# io-board-f-1.net
KiCad netlist of a schematic drawn in EAGLE
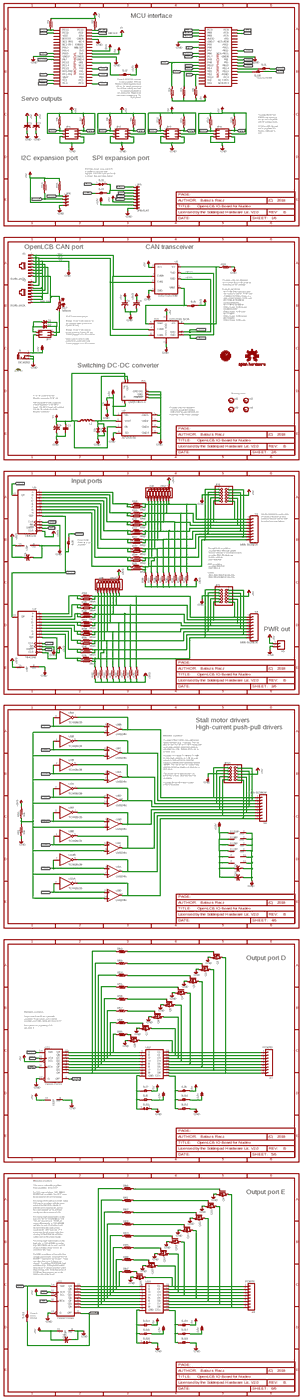
[diagram p0: schematic, sheet 1, overview]
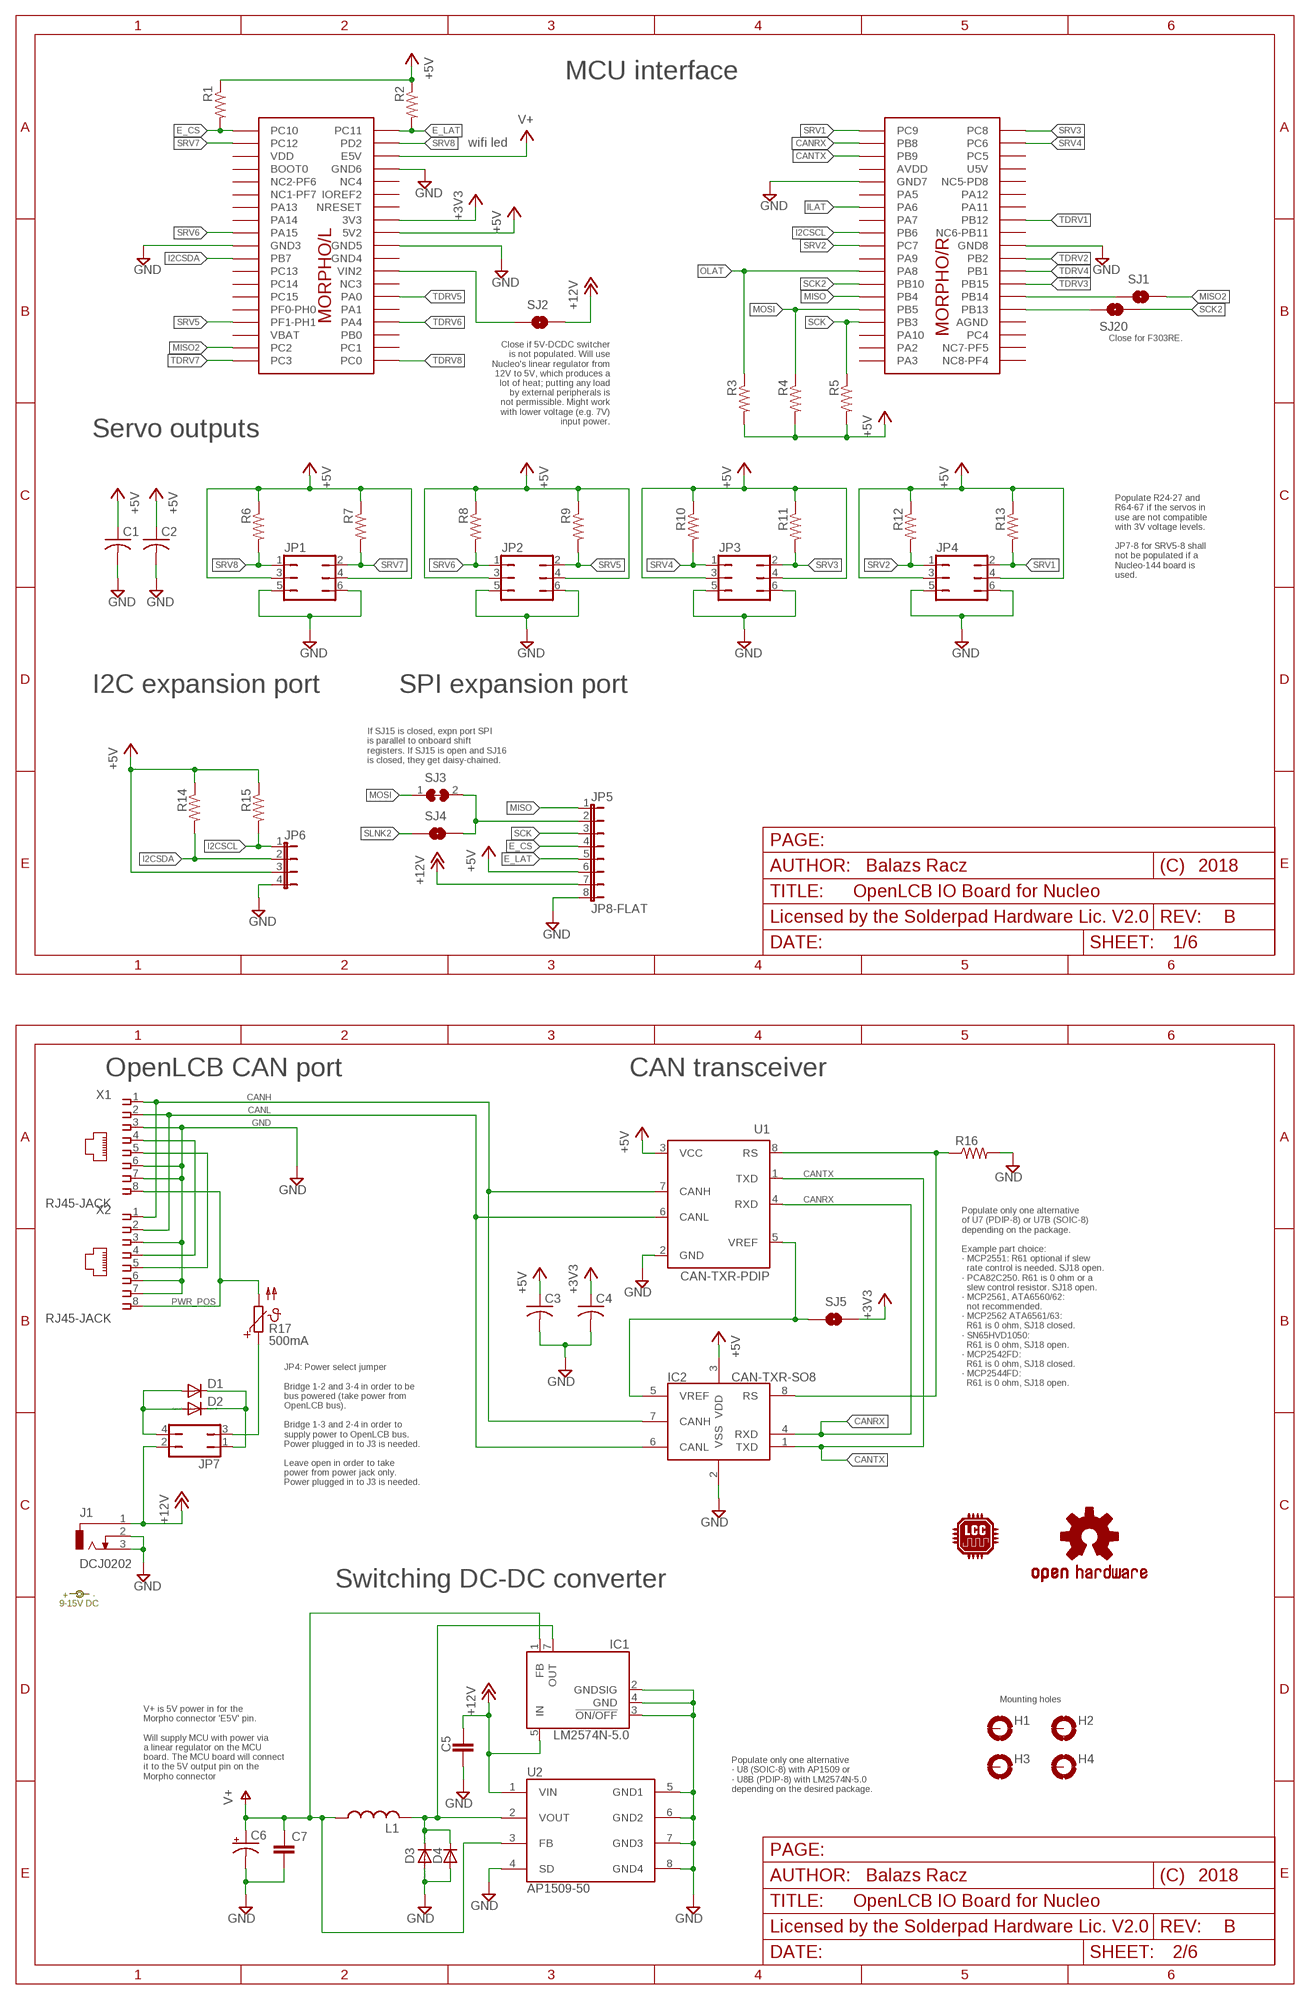
[diagram p1: schematic, sheet 1, part 1 of 4]
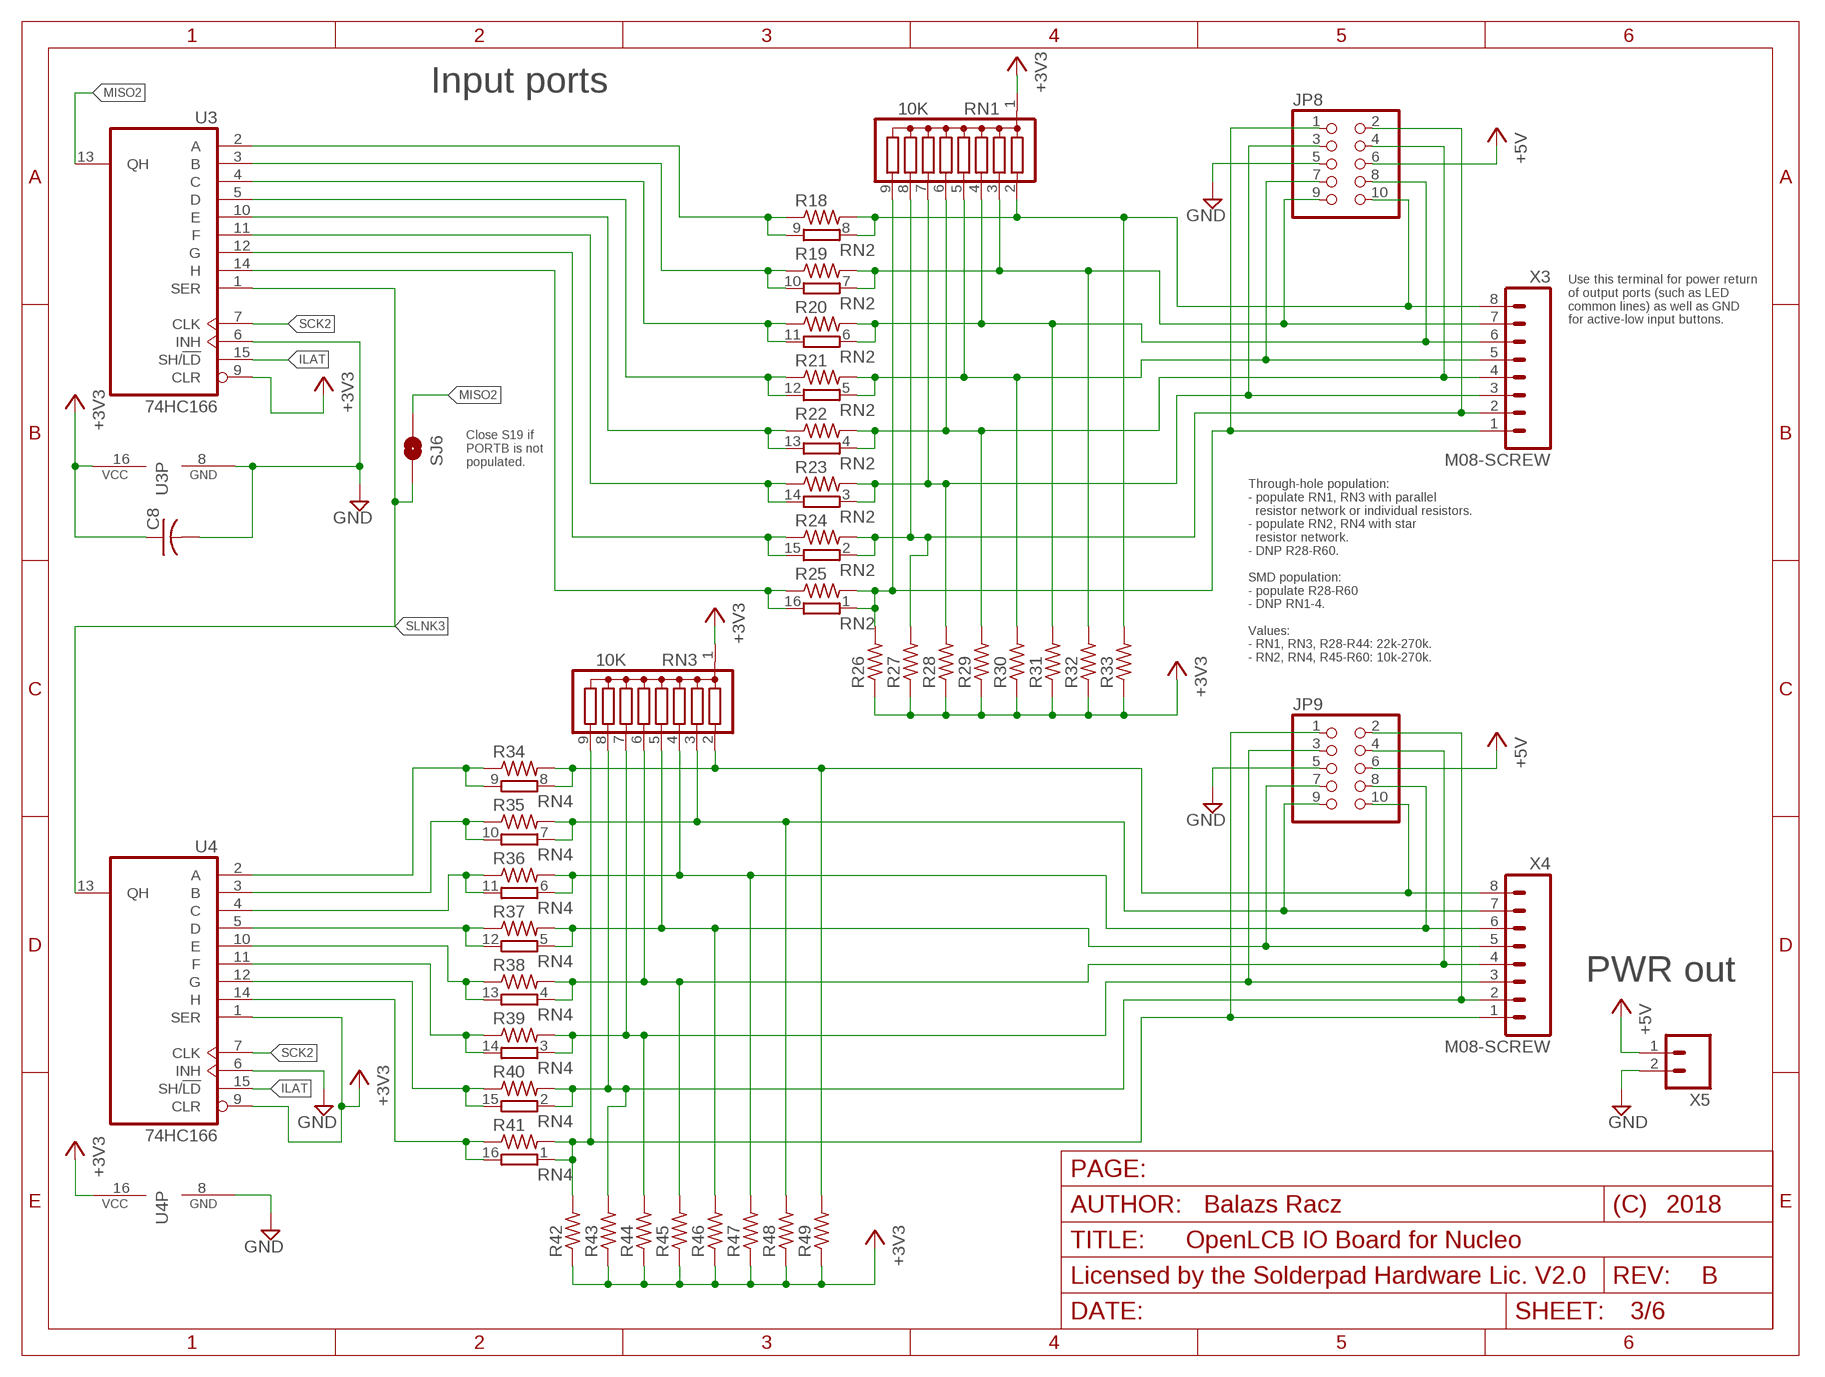
[diagram p2: schematic, sheet 1, part 2 of 4]
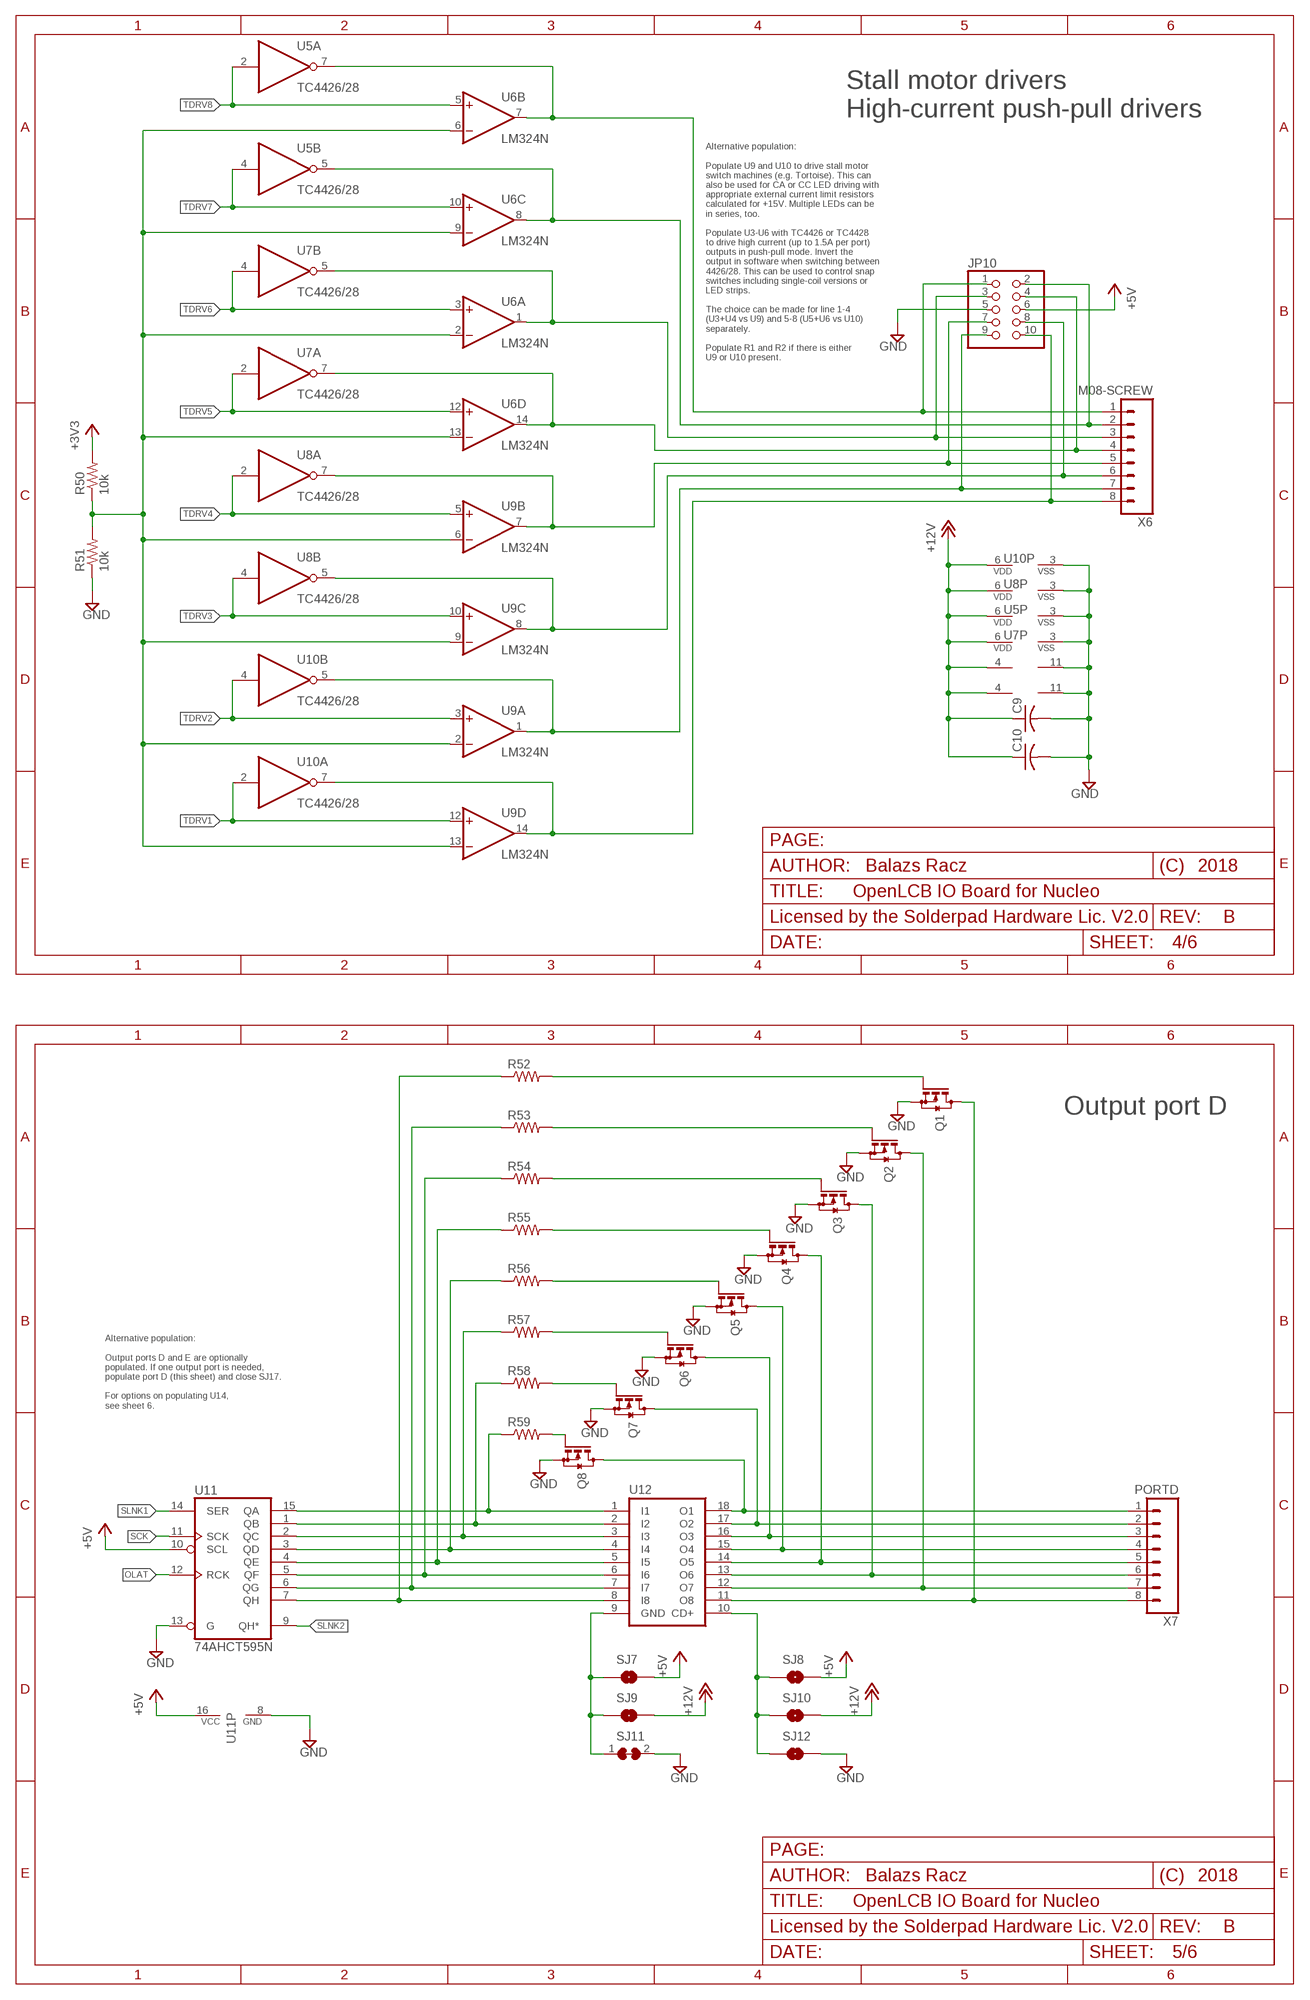
[diagram p3: schematic, sheet 1, part 3 of 4]
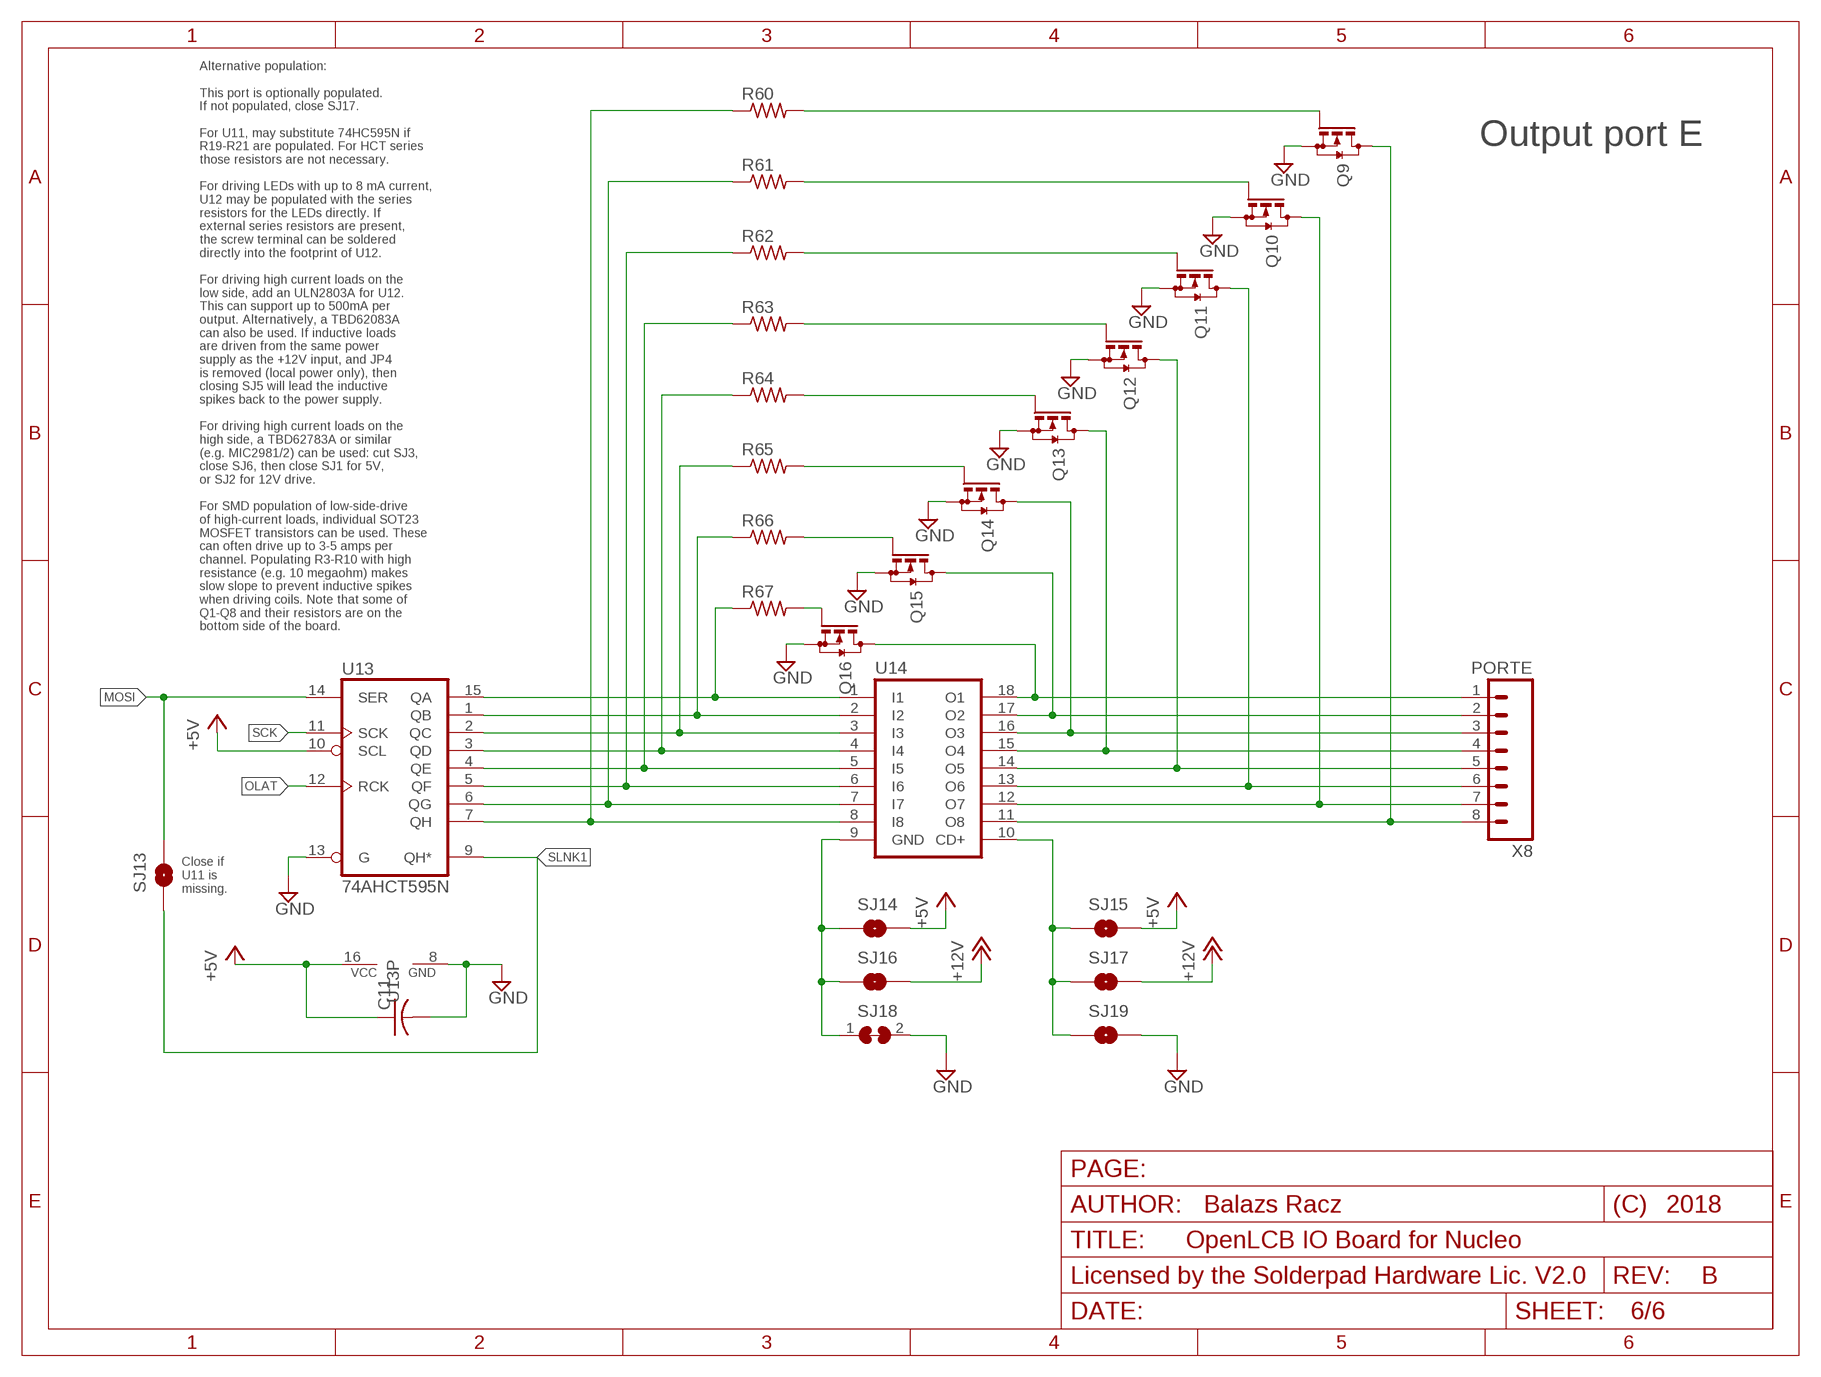
[diagram p4: schematic, sheet 1, part 4 of 4]

(export (version "E")
  (design (tool "Eeschema 10.0.6"))
  (components
    (comp (ref "C1")
      (value "C-USC1206")
      (footprint "eagle-import:C1206")
      (libsource (lib "eagle-import") (part "C-USC1206"))
    )
    (comp (ref "C2")
      (value "C-USC1206")
      (footprint "eagle-import:C1206")
      (libsource (lib "eagle-import") (part "C-USC1206"))
    )
    (comp (ref "C3")
      (value "C-USC0805")
      (footprint "eagle-import:C0805")
      (libsource (lib "eagle-import") (part "C-USC0805"))
    )
    (comp (ref "C4")
      (value "C-USC0805")
      (footprint "eagle-import:C0805")
      (libsource (lib "eagle-import") (part "C-USC0805"))
    )
    (comp (ref "C5")
      (value "C-EUC1206")
      (footprint "eagle-import:C1206")
      (libsource (lib "eagle-import") (part "C-EUC1206"))
    )
    (comp (ref "C6")
      (value "CPOL-USE2.5-5")
      (footprint "eagle-import:E2,5-5")
      (libsource (lib "eagle-import") (part "CPOL-USE2.5-5"))
    )
    (comp (ref "C7")
      (value "C-EUC1206")
      (footprint "eagle-import:C1206")
      (libsource (lib "eagle-import") (part "C-EUC1206"))
    )
    (comp (ref "C8")
      (value "C-USC0805")
      (footprint "eagle-import:C0805")
      (libsource (lib "eagle-import") (part "C-USC0805"))
    )
    (comp (ref "C9")
      (value "C-USC1206")
      (footprint "eagle-import:C1206")
      (libsource (lib "eagle-import") (part "C-USC1206"))
    )
    (comp (ref "C10")
      (value "C-USC1206")
      (footprint "eagle-import:C1206")
      (libsource (lib "eagle-import") (part "C-USC1206"))
    )
    (comp (ref "C11")
      (value "C-USC0805")
      (footprint "eagle-import:C0805")
      (libsource (lib "eagle-import") (part "C-USC0805"))
    )
    (comp (ref "D1")
      (value "DIODEDO-214AA-NODOC")
      (footprint "eagle-import:DO214AA-NODOC")
      (libsource (lib "eagle-import") (part "DIODEDO-214AA-NODOC"))
    )
    (comp (ref "D2")
      (value "DIODE-DO41-7.6")
      (footprint "eagle-import:DO41-7.6")
      (libsource (lib "eagle-import") (part "DIODE-DO41-7.6"))
    )
    (comp (ref "D3")
      (value "DIODE-DO41-7.6")
      (footprint "eagle-import:DO41-7.6")
      (libsource (lib "eagle-import") (part "DIODE-DO41-7.6"))
    )
    (comp (ref "D4")
      (value "DIODEDO-214AA-NODOC")
      (footprint "eagle-import:DO214AA-NODOC")
      (libsource (lib "eagle-import") (part "DIODEDO-214AA-NODOC"))
    )
    (comp (ref "G1")
      (value "NUCLEO_64_GENERIC")
      (footprint "eagle-import:NUCLEO_BRD_BASE64")
      (libsource (lib "eagle-import") (part "NUCLEO_64_GENERIC"))
    )
    (comp (ref "H1")
      (value "MOUNT-PAD-ROUND3.3")
      (footprint "eagle-import:3,3-PAD")
      (libsource (lib "eagle-import") (part "MOUNT-PAD-ROUND3.3"))
    )
    (comp (ref "H2")
      (value "MOUNT-PAD-ROUND3.3")
      (footprint "eagle-import:3,3-PAD")
      (libsource (lib "eagle-import") (part "MOUNT-PAD-ROUND3.3"))
    )
    (comp (ref "H3")
      (value "MOUNT-PAD-ROUND3.3")
      (footprint "eagle-import:3,3-PAD")
      (libsource (lib "eagle-import") (part "MOUNT-PAD-ROUND3.3"))
    )
    (comp (ref "H4")
      (value "MOUNT-PAD-ROUND3.3")
      (footprint "eagle-import:3,3-PAD")
      (libsource (lib "eagle-import") (part "MOUNT-PAD-ROUND3.3"))
    )
    (comp (ref "IC1")
      (value "LM2574N-5.0")
      (footprint "eagle-import:DIL08")
      (libsource (lib "eagle-import") (part "LM2574?-N5.0"))
    )
    (comp (ref "IC2")
      (value "CAN-TXR-SO8")
      (footprint "eagle-import:SO-08")
      (libsource (lib "eagle-import") (part "MCP2551-SN"))
    )
    (comp (ref "J1")
      (value "DCJ0202")
      (footprint "eagle-import:DCJ0202")
      (libsource (lib "eagle-import") (part "DCJ0202"))
    )
    (comp (ref "JP1")
      (value "JP3Q")
      (footprint "eagle-import:JP3Q")
      (libsource (lib "eagle-import") (part "JP3Q"))
    )
    (comp (ref "JP2")
      (value "JP3Q")
      (footprint "eagle-import:JP3Q")
      (libsource (lib "eagle-import") (part "JP3Q"))
    )
    (comp (ref "JP3")
      (value "JP3Q")
      (footprint "eagle-import:JP3Q")
      (libsource (lib "eagle-import") (part "JP3Q"))
    )
    (comp (ref "JP4")
      (value "JP3Q")
      (footprint "eagle-import:JP3Q")
      (libsource (lib "eagle-import") (part "JP3Q"))
    )
    (comp (ref "JP5")
      (value "JP8-FLAT")
      (footprint "eagle-import:JP8F")
      (libsource (lib "eagle-import") (part "JP8-FLAT"))
    )
    (comp (ref "JP6")
      (value "JP4-FLAT")
      (footprint "eagle-import:JP4F")
      (libsource (lib "eagle-import") (part "JP4-FLAT"))
    )
    (comp (ref "JP7")
      (value "JP2Q")
      (footprint "eagle-import:JP2Q")
      (libsource (lib "eagle-import") (part "JP2Q"))
    )
    (comp (ref "JP8")
      (value "PINHD-2X5CN")
      (footprint "eagle-import:CON10M")
      (libsource (lib "eagle-import") (part "PINHD-2X5CN"))
    )
    (comp (ref "JP9")
      (value "PINHD-2X5CN")
      (footprint "eagle-import:CON10M")
      (libsource (lib "eagle-import") (part "PINHD-2X5CN"))
    )
    (comp (ref "JP10")
      (value "PINHD-2X5CN")
      (footprint "eagle-import:CON10M")
      (libsource (lib "eagle-import") (part "PINHD-2X5CN"))
    )
    (comp (ref "L1")
      (value "L-US")
      (footprint "eagle-import:L5-8,5")
      (libsource (lib "eagle-import") (part "L-US"))
    )
    (comp (ref "LG1")
      (value "LCC_LOGO")
      (footprint "eagle-import:LCC_LOGO")
      (libsource (lib "eagle-import") (part "LCC_LOGO"))
    )
    (comp (ref "LOGO1")
      (value "DOC-OSHW-LOGOM")
      (footprint "eagle-import:OSHW-LOGO-M")
      (libsource (lib "eagle-import") (part "DOC-OSHW-LOGOM"))
    )
    (comp (ref "P1")
      (value "9-15V DC")
      (footprint "eagle-import:POWER_USAGE")
      (libsource (lib "eagle-import") (part "DOC-POWER_LABEL"))
    )
    (comp (ref "Q1")
      (value "BSS123")
      (footprint "eagle-import:SOT23")
      (libsource (lib "eagle-import") (part "BSS123"))
    )
    (comp (ref "Q2")
      (value "BSS123")
      (footprint "eagle-import:SOT23")
      (libsource (lib "eagle-import") (part "BSS123"))
    )
    (comp (ref "Q3")
      (value "BSS123")
      (footprint "eagle-import:SOT23")
      (libsource (lib "eagle-import") (part "BSS123"))
    )
    (comp (ref "Q4")
      (value "BSS123")
      (footprint "eagle-import:SOT23")
      (libsource (lib "eagle-import") (part "BSS123"))
    )
    (comp (ref "Q5")
      (value "BSS123")
      (footprint "eagle-import:SOT23")
      (libsource (lib "eagle-import") (part "BSS123"))
    )
    (comp (ref "Q6")
      (value "BSS123")
      (footprint "eagle-import:SOT23")
      (libsource (lib "eagle-import") (part "BSS123"))
    )
    (comp (ref "Q7")
      (value "BSS123")
      (footprint "eagle-import:SOT23")
      (libsource (lib "eagle-import") (part "BSS123"))
    )
    (comp (ref "Q8")
      (value "BSS123")
      (footprint "eagle-import:SOT23")
      (libsource (lib "eagle-import") (part "BSS123"))
    )
    (comp (ref "Q9")
      (value "BSS123")
      (footprint "eagle-import:SOT23")
      (libsource (lib "eagle-import") (part "BSS123"))
    )
    (comp (ref "Q10")
      (value "BSS123")
      (footprint "eagle-import:SOT23")
      (libsource (lib "eagle-import") (part "BSS123"))
    )
    (comp (ref "Q11")
      (value "BSS123")
      (footprint "eagle-import:SOT23")
      (libsource (lib "eagle-import") (part "BSS123"))
    )
    (comp (ref "Q12")
      (value "BSS123")
      (footprint "eagle-import:SOT23")
      (libsource (lib "eagle-import") (part "BSS123"))
    )
    (comp (ref "Q13")
      (value "BSS123")
      (footprint "eagle-import:SOT23")
      (libsource (lib "eagle-import") (part "BSS123"))
    )
    (comp (ref "Q14")
      (value "BSS123")
      (footprint "eagle-import:SOT23")
      (libsource (lib "eagle-import") (part "BSS123"))
    )
    (comp (ref "Q15")
      (value "BSS123")
      (footprint "eagle-import:SOT23")
      (libsource (lib "eagle-import") (part "BSS123"))
    )
    (comp (ref "Q16")
      (value "BSS123")
      (footprint "eagle-import:SOT23")
      (libsource (lib "eagle-import") (part "BSS123"))
    )
    (comp (ref "R1")
      (value "R-US_R0805")
      (footprint "eagle-import:R0805")
      (libsource (lib "eagle-import") (part "rcl_334_R-US_R0805"))
    )
    (comp (ref "R2")
      (value "R-US_R0805")
      (footprint "eagle-import:R0805")
      (libsource (lib "eagle-import") (part "rcl_334_R-US_R0805"))
    )
    (comp (ref "R3")
      (value "R-US_R0805")
      (footprint "eagle-import:R0805")
      (libsource (lib "eagle-import") (part "rcl_334_R-US_R0805"))
    )
    (comp (ref "R4")
      (value "R-US_R0805")
      (footprint "eagle-import:R0805")
      (libsource (lib "eagle-import") (part "rcl_334_R-US_R0805"))
    )
    (comp (ref "R5")
      (value "R-US_R0805")
      (footprint "eagle-import:R0805")
      (libsource (lib "eagle-import") (part "rcl_334_R-US_R0805"))
    )
    (comp (ref "R6")
      (value "R-US_R0805")
      (footprint "eagle-import:R0805")
      (libsource (lib "eagle-import") (part "rcl_334_R-US_R0805"))
    )
    (comp (ref "R7")
      (value "R-US_R0805")
      (footprint "eagle-import:R0805")
      (libsource (lib "eagle-import") (part "rcl_334_R-US_R0805"))
    )
    (comp (ref "R8")
      (value "R-US_R0805")
      (footprint "eagle-import:R0805")
      (libsource (lib "eagle-import") (part "rcl_334_R-US_R0805"))
    )
    (comp (ref "R9")
      (value "R-US_R0805")
      (footprint "eagle-import:R0805")
      (libsource (lib "eagle-import") (part "rcl_334_R-US_R0805"))
    )
    (comp (ref "R10")
      (value "R-US_R0805")
      (footprint "eagle-import:R0805")
      (libsource (lib "eagle-import") (part "rcl_334_R-US_R0805"))
    )
    (comp (ref "R11")
      (value "R-US_R0805")
      (footprint "eagle-import:R0805")
      (libsource (lib "eagle-import") (part "rcl_334_R-US_R0805"))
    )
    (comp (ref "R12")
      (value "R-US_R0805")
      (footprint "eagle-import:R0805")
      (libsource (lib "eagle-import") (part "rcl_334_R-US_R0805"))
    )
    (comp (ref "R13")
      (value "R-US_R0805")
      (footprint "eagle-import:R0805")
      (libsource (lib "eagle-import") (part "rcl_334_R-US_R0805"))
    )
    (comp (ref "R14")
      (value "R-US_R0805")
      (footprint "eagle-import:R0805")
      (libsource (lib "eagle-import") (part "rcl_334_R-US_R0805"))
    )
    (comp (ref "R15")
      (value "R-US_R0805")
      (footprint "eagle-import:R0805")
      (libsource (lib "eagle-import") (part "rcl_334_R-US_R0805"))
    )
    (comp (ref "R16")
      (value "R-US_R0805")
      (footprint "eagle-import:R0805")
      (libsource (lib "eagle-import") (part "rcl_334_R-US_R0805"))
    )
    (comp (ref "R17")
      (value "500mA")
      (footprint "eagle-import:PTC1812")
      (libsource (lib "eagle-import") (part "PTC_1812"))
    )
    (comp (ref "R18")
      (value "R-US_R0603")
      (footprint "eagle-import:R0603")
      (libsource (lib "eagle-import") (part "rcl_334_R-US_R0603"))
    )
    (comp (ref "R19")
      (value "R-US_R0603")
      (footprint "eagle-import:R0603")
      (libsource (lib "eagle-import") (part "rcl_334_R-US_R0603"))
    )
    (comp (ref "R20")
      (value "R-US_R0603")
      (footprint "eagle-import:R0603")
      (libsource (lib "eagle-import") (part "rcl_334_R-US_R0603"))
    )
    (comp (ref "R21")
      (value "R-US_R0603")
      (footprint "eagle-import:R0603")
      (libsource (lib "eagle-import") (part "rcl_334_R-US_R0603"))
    )
    (comp (ref "R22")
      (value "R-US_R0603")
      (footprint "eagle-import:R0603")
      (libsource (lib "eagle-import") (part "rcl_334_R-US_R0603"))
    )
    (comp (ref "R23")
      (value "R-US_R0603")
      (footprint "eagle-import:R0603")
      (libsource (lib "eagle-import") (part "rcl_334_R-US_R0603"))
    )
    (comp (ref "R24")
      (value "R-US_R0603")
      (footprint "eagle-import:R0603")
      (libsource (lib "eagle-import") (part "rcl_334_R-US_R0603"))
    )
    (comp (ref "R25")
      (value "R-US_R0603")
      (footprint "eagle-import:R0603")
      (libsource (lib "eagle-import") (part "rcl_334_R-US_R0603"))
    )
    (comp (ref "R26")
      (value "R-US")
      (footprint "eagle-import:R0603")
      (libsource (lib "eagle-import") (part "R-US"))
    )
    (comp (ref "R27")
      (value "R-US")
      (footprint "eagle-import:R0603")
      (libsource (lib "eagle-import") (part "R-US"))
    )
    (comp (ref "R28")
      (value "R-US")
      (footprint "eagle-import:R0603")
      (libsource (lib "eagle-import") (part "R-US"))
    )
    (comp (ref "R29")
      (value "R-US")
      (footprint "eagle-import:R0603")
      (libsource (lib "eagle-import") (part "R-US"))
    )
    (comp (ref "R30")
      (value "R-US")
      (footprint "eagle-import:R0603")
      (libsource (lib "eagle-import") (part "R-US"))
    )
    (comp (ref "R31")
      (value "R-US")
      (footprint "eagle-import:R0603")
      (libsource (lib "eagle-import") (part "R-US"))
    )
    (comp (ref "R32")
      (value "R-US")
      (footprint "eagle-import:R0603")
      (libsource (lib "eagle-import") (part "R-US"))
    )
    (comp (ref "R33")
      (value "R-US")
      (footprint "eagle-import:R0603")
      (libsource (lib "eagle-import") (part "R-US"))
    )
    (comp (ref "R34")
      (value "R-US_R0603")
      (footprint "eagle-import:R0603")
      (libsource (lib "eagle-import") (part "rcl_334_R-US_R0603"))
    )
    (comp (ref "R35")
      (value "R-US_R0603")
      (footprint "eagle-import:R0603")
      (libsource (lib "eagle-import") (part "rcl_334_R-US_R0603"))
    )
    (comp (ref "R36")
      (value "R-US_R0603")
      (footprint "eagle-import:R0603")
      (libsource (lib "eagle-import") (part "rcl_334_R-US_R0603"))
    )
    (comp (ref "R37")
      (value "R-US_R0603")
      (footprint "eagle-import:R0603")
      (libsource (lib "eagle-import") (part "rcl_334_R-US_R0603"))
    )
    (comp (ref "R38")
      (value "R-US_R0603")
      (footprint "eagle-import:R0603")
      (libsource (lib "eagle-import") (part "rcl_334_R-US_R0603"))
    )
    (comp (ref "R39")
      (value "R-US_R0603")
      (footprint "eagle-import:R0603")
      (libsource (lib "eagle-import") (part "rcl_334_R-US_R0603"))
    )
    (comp (ref "R40")
      (value "R-US_R0603")
      (footprint "eagle-import:R0603")
      (libsource (lib "eagle-import") (part "rcl_334_R-US_R0603"))
    )
    (comp (ref "R41")
      (value "R-US_R0603")
      (footprint "eagle-import:R0603")
      (libsource (lib "eagle-import") (part "rcl_334_R-US_R0603"))
    )
    (comp (ref "R42")
      (value "R-US")
      (footprint "eagle-import:R0603")
      (libsource (lib "eagle-import") (part "R-US"))
    )
    (comp (ref "R43")
      (value "R-US")
      (footprint "eagle-import:R0603")
      (libsource (lib "eagle-import") (part "R-US"))
    )
    (comp (ref "R44")
      (value "R-US")
      (footprint "eagle-import:R0603")
      (libsource (lib "eagle-import") (part "R-US"))
    )
    (comp (ref "R45")
      (value "R-US")
      (footprint "eagle-import:R0603")
      (libsource (lib "eagle-import") (part "R-US"))
    )
    (comp (ref "R46")
      (value "R-US")
      (footprint "eagle-import:R0603")
      (libsource (lib "eagle-import") (part "R-US"))
    )
    (comp (ref "R47")
      (value "R-US")
      (footprint "eagle-import:R0603")
      (libsource (lib "eagle-import") (part "R-US"))
    )
    (comp (ref "R48")
      (value "R-US")
      (footprint "eagle-import:R0603")
      (libsource (lib "eagle-import") (part "R-US"))
    )
    (comp (ref "R49")
      (value "R-US")
      (footprint "eagle-import:R0603")
      (libsource (lib "eagle-import") (part "R-US"))
    )
    (comp (ref "R50")
      (value "10k")
      (footprint "eagle-import:R0805")
      (libsource (lib "eagle-import") (part "R-US_R0805"))
    )
    (comp (ref "R51")
      (value "10k")
      (footprint "eagle-import:R0805")
      (libsource (lib "eagle-import") (part "R-US_R0805"))
    )
    (comp (ref "R52")
      (value "R-US_R0603")
      (footprint "eagle-import:R0603")
      (libsource (lib "eagle-import") (part "R-US_R0603"))
    )
    (comp (ref "R53")
      (value "R-US_R0603")
      (footprint "eagle-import:R0603")
      (libsource (lib "eagle-import") (part "R-US_R0603"))
    )
    (comp (ref "R54")
      (value "R-US_R0603")
      (footprint "eagle-import:R0603")
      (libsource (lib "eagle-import") (part "R-US_R0603"))
    )
    (comp (ref "R55")
      (value "R-US_R0603")
      (footprint "eagle-import:R0603")
      (libsource (lib "eagle-import") (part "R-US_R0603"))
    )
    (comp (ref "R56")
      (value "R-US_R0603")
      (footprint "eagle-import:R0603")
      (libsource (lib "eagle-import") (part "R-US_R0603"))
    )
    (comp (ref "R57")
      (value "R-US_R0603")
      (footprint "eagle-import:R0603")
      (libsource (lib "eagle-import") (part "R-US_R0603"))
    )
    (comp (ref "R58")
      (value "R-US_R0603")
      (footprint "eagle-import:R0603")
      (libsource (lib "eagle-import") (part "R-US_R0603"))
    )
    (comp (ref "R59")
      (value "R-US_R0603")
      (footprint "eagle-import:R0603")
      (libsource (lib "eagle-import") (part "R-US_R0603"))
    )
    (comp (ref "R60")
      (value "R-US_R0603")
      (footprint "eagle-import:R0603")
      (libsource (lib "eagle-import") (part "R-US_R0603"))
    )
    (comp (ref "R61")
      (value "R-US_R0603")
      (footprint "eagle-import:R0603")
      (libsource (lib "eagle-import") (part "R-US_R0603"))
    )
    (comp (ref "R62")
      (value "R-US_R0603")
      (footprint "eagle-import:R0603")
      (libsource (lib "eagle-import") (part "R-US_R0603"))
    )
    (comp (ref "R63")
      (value "R-US_R0603")
      (footprint "eagle-import:R0603")
      (libsource (lib "eagle-import") (part "R-US_R0603"))
    )
    (comp (ref "R64")
      (value "R-US_R0603")
      (footprint "eagle-import:R0603")
      (libsource (lib "eagle-import") (part "R-US_R0603"))
    )
    (comp (ref "R65")
      (value "R-US_R0603")
      (footprint "eagle-import:R0603")
      (libsource (lib "eagle-import") (part "R-US_R0603"))
    )
    (comp (ref "R66")
      (value "R-US_R0603")
      (footprint "eagle-import:R0603")
      (libsource (lib "eagle-import") (part "R-US_R0603"))
    )
    (comp (ref "R67")
      (value "R-US_R0603")
      (footprint "eagle-import:R0603")
      (libsource (lib "eagle-import") (part "R-US_R0603"))
    )
    (comp (ref "RN1")
      (value "10K")
      (footprint "eagle-import:SIL9")
      (libsource (lib "eagle-import") (part "G08R"))
    )
    (comp (ref "RN2")
      (value "8R-P")
      (footprint "eagle-import:DIL16")
      (libsource (lib "eagle-import") (part "8R-P"))
    )
    (comp (ref "RN3")
      (value "10K")
      (footprint "eagle-import:SIL9")
      (libsource (lib "eagle-import") (part "G08R"))
    )
    (comp (ref "RN4")
      (value "8R-P")
      (footprint "eagle-import:DIL16")
      (libsource (lib "eagle-import") (part "8R-P"))
    )
    (comp (ref "SJ1")
      (value "SJRND2")
      (footprint "eagle-import:SJ_RND2")
      (libsource (lib "eagle-import") (part "SJRND2"))
    )
    (comp (ref "SJ2")
      (value "SJRND2")
      (footprint "eagle-import:SJ_RND2")
      (libsource (lib "eagle-import") (part "SJRND2"))
    )
    (comp (ref "SJ3")
      (value "SJ-C")
      (footprint "eagle-import:SJW-C")
      (libsource (lib "eagle-import") (part "SJ-C"))
    )
    (comp (ref "SJ4")
      (value "SJRND2")
      (footprint "eagle-import:SJ_RND2")
      (libsource (lib "eagle-import") (part "SJRND2"))
    )
    (comp (ref "SJ5")
      (value "SJRND2")
      (footprint "eagle-import:SJ_RND2")
      (libsource (lib "eagle-import") (part "SJRND2"))
    )
    (comp (ref "SJ6")
      (value "SJRND2")
      (footprint "eagle-import:SJ_RND2")
      (libsource (lib "eagle-import") (part "SJRND2"))
    )
    (comp (ref "SJ7")
      (value "SJRND2")
      (footprint "eagle-import:SJ_RND2")
      (libsource (lib "eagle-import") (part "SJRND2"))
    )
    (comp (ref "SJ8")
      (value "SJRND2")
      (footprint "eagle-import:SJ_RND2")
      (libsource (lib "eagle-import") (part "SJRND2"))
    )
    (comp (ref "SJ9")
      (value "SJRND2")
      (footprint "eagle-import:SJ_RND2")
      (libsource (lib "eagle-import") (part "SJRND2"))
    )
    (comp (ref "SJ10")
      (value "SJRND2")
      (footprint "eagle-import:SJ_RND2")
      (libsource (lib "eagle-import") (part "SJRND2"))
    )
    (comp (ref "SJ11")
      (value "SJ-C")
      (footprint "eagle-import:SJW-C")
      (libsource (lib "eagle-import") (part "SJ-C"))
    )
    (comp (ref "SJ12")
      (value "SJRND2")
      (footprint "eagle-import:SJ_RND2")
      (libsource (lib "eagle-import") (part "SJRND2"))
    )
    (comp (ref "SJ13")
      (value "SJRND2")
      (footprint "eagle-import:SJ_RND2")
      (libsource (lib "eagle-import") (part "SJRND2"))
    )
    (comp (ref "SJ14")
      (value "SJRND2")
      (footprint "eagle-import:SJ_RND2")
      (libsource (lib "eagle-import") (part "SJRND2"))
    )
    (comp (ref "SJ15")
      (value "SJRND2")
      (footprint "eagle-import:SJ_RND2")
      (libsource (lib "eagle-import") (part "SJRND2"))
    )
    (comp (ref "SJ16")
      (value "SJRND2")
      (footprint "eagle-import:SJ_RND2")
      (libsource (lib "eagle-import") (part "SJRND2"))
    )
    (comp (ref "SJ17")
      (value "SJRND2")
      (footprint "eagle-import:SJ_RND2")
      (libsource (lib "eagle-import") (part "SJRND2"))
    )
    (comp (ref "SJ18")
      (value "SJ-C")
      (footprint "eagle-import:SJW-C")
      (libsource (lib "eagle-import") (part "SJ-C"))
    )
    (comp (ref "SJ19")
      (value "SJRND2")
      (footprint "eagle-import:SJ_RND2")
      (libsource (lib "eagle-import") (part "SJRND2"))
    )
    (comp (ref "SJ20")
      (value "SJRND2")
      (footprint "eagle-import:SJ_RND2")
      (libsource (lib "eagle-import") (part "SJRND2"))
    )
    (comp (ref "U1")
      (value "CAN-TXR-PDIP")
      (footprint "eagle-import:DIL08")
      (libsource (lib "eagle-import") (part "PCA82C250"))
    )
    (comp (ref "U2")
      (value "AP1509-50")
      (footprint "eagle-import:SO-08")
      (libsource (lib "eagle-import") (part "AP1509"))
    )
    (comp (ref "U3")
      (value "74HC166")
      (footprint "eagle-import:DIL16")
      (libsource (lib "eagle-import") (part "74166N"))
    )
    (comp (ref "U4")
      (value "74HC166")
      (footprint "eagle-import:DIL16")
      (libsource (lib "eagle-import") (part "74166N"))
    )
    (comp (ref "U5")
      (value "TC4426/28")
      (footprint "eagle-import:DIL08-LONG")
      (libsource (lib "eagle-import") (part "TC4426APDIP"))
    )
    (comp (ref "U6")
      (value "LM324N")
      (footprint "eagle-import:DIL14")
      (libsource (lib "eagle-import") (part "LM324N"))
    )
    (comp (ref "U7")
      (value "TC4426/28")
      (footprint "eagle-import:DIL08-LONG")
      (libsource (lib "eagle-import") (part "TC4426APDIP"))
    )
    (comp (ref "U8")
      (value "TC4426/28")
      (footprint "eagle-import:DIL08-LONG")
      (libsource (lib "eagle-import") (part "TC4426APDIP"))
    )
    (comp (ref "U9")
      (value "LM324N")
      (footprint "eagle-import:DIL14")
      (libsource (lib "eagle-import") (part "LM324N"))
    )
    (comp (ref "U10")
      (value "TC4426/28")
      (footprint "eagle-import:DIL08-LONG")
      (libsource (lib "eagle-import") (part "TC4426APDIP"))
    )
    (comp (ref "U11")
      (value "74AHCT595N")
      (footprint "eagle-import:DIL16")
      (libsource (lib "eagle-import") (part "74595NHCT"))
    )
    (comp (ref "U12")
      (value "ULN2803A")
      (footprint "eagle-import:DIL18-THIN")
      (libsource (lib "eagle-import") (part "ULN2803A"))
    )
    (comp (ref "U13")
      (value "74AHCT595N")
      (footprint "eagle-import:DIL16")
      (libsource (lib "eagle-import") (part "74595NHCT"))
    )
    (comp (ref "U14")
      (value "ULN2803A")
      (footprint "eagle-import:DIL18-THIN")
      (libsource (lib "eagle-import") (part "ULN2803A"))
    )
    (comp (ref "X1")
      (value "RJ45-JACK")
      (footprint "eagle-import:RJ45-PULSE-E5J88")
      (libsource (lib "eagle-import") (part "RJ45-JACKRJ45-PULSE-E5J00"))
    )
    (comp (ref "X2")
      (value "RJ45-JACK")
      (footprint "eagle-import:RJ45-PULSE-E5J88")
      (libsource (lib "eagle-import") (part "RJ45-JACKRJ45-PULSE-E5J00"))
    )
    (comp (ref "X3")
      (value "M08-SCREW")
      (footprint "eagle-import:1X08_TERMINAL")
      (libsource (lib "eagle-import") (part "M08-SCREW"))
    )
    (comp (ref "X4")
      (value "M08-SCREW")
      (footprint "eagle-import:1X08_TERMINAL")
      (libsource (lib "eagle-import") (part "M08-SCREW"))
    )
    (comp (ref "X5")
      (value "CONNECTOR-M023.5MM-LOCK")
      (footprint "eagle-import:SCREWTERMINAL-3.5MM-2_LOCK")
      (libsource (lib "eagle-import") (part "CONNECTOR-M023.5MM-LOCK"))
    )
    (comp (ref "X6")
      (value "M08-SCREW")
      (footprint "eagle-import:1X08_TERMINAL")
      (libsource (lib "eagle-import") (part "M08-SCREW"))
    )
    (comp (ref "X7")
      (value "PORTD")
      (footprint "eagle-import:1X08_TERMINAL")
      (libsource (lib "eagle-import") (part "M08-SCREW"))
    )
    (comp (ref "X8")
      (value "PORTE")
      (footprint "eagle-import:1X08_TERMINAL")
      (libsource (lib "eagle-import") (part "M08-SCREW"))
    )
  )
  (nets
    (net (code "1") (name "+3V3") (class "Default")
      (node (ref "C4") (pin "1") (pinfunction "1_1") (pintype "passive"))
      (node (ref "C8") (pin "1") (pinfunction "1_1") (pintype "passive"))
      (node (ref "G1") (pin "3V3") (pinfunction "3V3_3V3") (pintype "power_in"))
      (node (ref "R26") (pin "1") (pinfunction "1_1") (pintype "passive"))
      (node (ref "R27") (pin "1") (pinfunction "1_1") (pintype "passive"))
      (node (ref "R28") (pin "1") (pinfunction "1_1") (pintype "passive"))
      (node (ref "R29") (pin "1") (pinfunction "1_1") (pintype "passive"))
      (node (ref "R30") (pin "1") (pinfunction "1_1") (pintype "passive"))
      (node (ref "R31") (pin "1") (pinfunction "1_1") (pintype "passive"))
      (node (ref "R32") (pin "1") (pinfunction "1_1") (pintype "passive"))
      (node (ref "R33") (pin "1") (pinfunction "1_1") (pintype "passive"))
      (node (ref "R42") (pin "1") (pinfunction "1_1") (pintype "passive"))
      (node (ref "R43") (pin "1") (pinfunction "1_1") (pintype "passive"))
      (node (ref "R44") (pin "1") (pinfunction "1_1") (pintype "passive"))
      (node (ref "R45") (pin "1") (pinfunction "1_1") (pintype "passive"))
      (node (ref "R46") (pin "1") (pinfunction "1_1") (pintype "passive"))
      (node (ref "R47") (pin "1") (pinfunction "1_1") (pintype "passive"))
      (node (ref "R48") (pin "1") (pinfunction "1_1") (pintype "passive"))
      (node (ref "R49") (pin "1") (pinfunction "1_1") (pintype "passive"))
      (node (ref "R50") (pin "2") (pinfunction "2_2") (pintype "passive"))
      (node (ref "RN1") (pin "1") (pinfunction "1_1") (pintype "passive"))
      (node (ref "RN3") (pin "1") (pinfunction "1_1") (pintype "passive"))
      (node (ref "SJ5") (pin "P$1") (pinfunction "1_P$1") (pintype "passive"))
      (node (ref "U3") (pin "16") (pinfunction "VCC_16") (pintype "power_in"))
      (node (ref "U3") (pin "9") (pinfunction "CLR_9") (pintype "input"))
      (node (ref "U4") (pin "1") (pinfunction "SER_1") (pintype "input"))
      (node (ref "U4") (pin "16") (pinfunction "VCC_16") (pintype "power_in"))
      (node (ref "U4") (pin "9") (pinfunction "CLR_9") (pintype "input"))
    )
    (net (code "2") (name "+5V") (class "Default")
      (node (ref "C1") (pin "1") (pinfunction "1_1") (pintype "passive"))
      (node (ref "C11") (pin "1") (pinfunction "1_1") (pintype "passive"))
      (node (ref "C2") (pin "1") (pinfunction "1_1") (pintype "passive"))
      (node (ref "C3") (pin "1") (pinfunction "1_1") (pintype "passive"))
      (node (ref "G1") (pin "5V2") (pinfunction "5V2_5V2") (pintype "power_in"))
      (node (ref "IC2") (pin "3") (pinfunction "VDD_3") (pintype "power_in"))
      (node (ref "JP1") (pin "3") (pinfunction "3_3") (pintype "passive"))
      (node (ref "JP1") (pin "4") (pinfunction "4_4") (pintype "passive"))
      (node (ref "JP10") (pin "6") (pinfunction "6_6") (pintype "passive"))
      (node (ref "JP2") (pin "3") (pinfunction "3_3") (pintype "passive"))
      (node (ref "JP2") (pin "4") (pinfunction "4_4") (pintype "passive"))
      (node (ref "JP3") (pin "3") (pinfunction "3_3") (pintype "passive"))
      (node (ref "JP3") (pin "4") (pinfunction "4_4") (pintype "passive"))
      (node (ref "JP4") (pin "3") (pinfunction "3_3") (pintype "passive"))
      (node (ref "JP4") (pin "4") (pinfunction "4_4") (pintype "passive"))
      (node (ref "JP5") (pin "6") (pinfunction "6_6") (pintype "passive"))
      (node (ref "JP6") (pin "3") (pinfunction "3_3") (pintype "passive"))
      (node (ref "JP8") (pin "6") (pinfunction "6_6") (pintype "passive"))
      (node (ref "JP9") (pin "6") (pinfunction "6_6") (pintype "passive"))
      (node (ref "R1") (pin "1") (pinfunction "1_1") (pintype "passive"))
      (node (ref "R10") (pin "1") (pinfunction "1_1") (pintype "passive"))
      (node (ref "R11") (pin "1") (pinfunction "1_1") (pintype "passive"))
      (node (ref "R12") (pin "1") (pinfunction "1_1") (pintype "passive"))
      (node (ref "R13") (pin "1") (pinfunction "1_1") (pintype "passive"))
      (node (ref "R14") (pin "1") (pinfunction "1_1") (pintype "passive"))
      (node (ref "R15") (pin "1") (pinfunction "1_1") (pintype "passive"))
      (node (ref "R2") (pin "1") (pinfunction "1_1") (pintype "passive"))
      (node (ref "R3") (pin "2") (pinfunction "2_2") (pintype "passive"))
      (node (ref "R4") (pin "2") (pinfunction "2_2") (pintype "passive"))
      (node (ref "R5") (pin "2") (pinfunction "2_2") (pintype "passive"))
      (node (ref "R6") (pin "1") (pinfunction "1_1") (pintype "passive"))
      (node (ref "R7") (pin "1") (pinfunction "1_1") (pintype "passive"))
      (node (ref "R8") (pin "1") (pinfunction "1_1") (pintype "passive"))
      (node (ref "R9") (pin "1") (pinfunction "1_1") (pintype "passive"))
      (node (ref "SJ14") (pin "P$2") (pinfunction "2_P$2") (pintype "passive"))
      (node (ref "SJ15") (pin "P$2") (pinfunction "2_P$2") (pintype "passive"))
      (node (ref "SJ7") (pin "P$2") (pinfunction "2_P$2") (pintype "passive"))
      (node (ref "SJ8") (pin "P$2") (pinfunction "2_P$2") (pintype "passive"))
      (node (ref "U1") (pin "3") (pinfunction "VCC_3") (pintype "power_in"))
      (node (ref "U11") (pin "10") (pinfunction "SCL_10") (pintype "input"))
      (node (ref "U11") (pin "16") (pinfunction "VCC_16") (pintype "power_in"))
      (node (ref "U13") (pin "10") (pinfunction "SCL_10") (pintype "input"))
      (node (ref "U13") (pin "16") (pinfunction "VCC_16") (pintype "power_in"))
      (node (ref "X5") (pin "1") (pinfunction "1_1") (pintype "passive"))
    )
    (net (code "3") (name "+12V") (class "Default")
      (node (ref "C10") (pin "1") (pinfunction "1_1") (pintype "passive"))
      (node (ref "C5") (pin "1") (pinfunction "1_1") (pintype "passive"))
      (node (ref "C9") (pin "1") (pinfunction "1_1") (pintype "passive"))
      (node (ref "IC1") (pin "5") (pinfunction "IN_5") (pintype "input"))
      (node (ref "J1") (pin "1") (pinfunction "1_1") (pintype "passive"))
      (node (ref "JP5") (pin "7") (pinfunction "7_7") (pintype "passive"))
      (node (ref "JP7") (pin "2") (pinfunction "2_2") (pintype "passive"))
      (node (ref "SJ10") (pin "P$2") (pinfunction "2_P$2") (pintype "passive"))
      (node (ref "SJ16") (pin "P$2") (pinfunction "2_P$2") (pintype "passive"))
      (node (ref "SJ17") (pin "P$2") (pinfunction "2_P$2") (pintype "passive"))
      (node (ref "SJ2") (pin "P$2") (pinfunction "2_P$2") (pintype "passive"))
      (node (ref "SJ9") (pin "P$2") (pinfunction "2_P$2") (pintype "passive"))
      (node (ref "U10") (pin "6") (pinfunction "VDD_6") (pintype "power_in"))
      (node (ref "U2") (pin "1") (pinfunction "VIN_1") (pintype "bidirectional"))
      (node (ref "U5") (pin "6") (pinfunction "VDD_6") (pintype "power_in"))
      (node (ref "U6") (pin "4") (pinfunction "V+_4") (pintype "power_in"))
      (node (ref "U7") (pin "6") (pinfunction "VDD_6") (pintype "power_in"))
      (node (ref "U8") (pin "6") (pinfunction "VDD_6") (pintype "power_in"))
      (node (ref "U9") (pin "4") (pinfunction "V+_4") (pintype "power_in"))
    )
    (net (code "4") (name "/AGND") (class "Default")
      (node (ref "G1") (pin "AGND") (pinfunction "AGND_AGND") (pintype "power_in"))
    )
    (net (code "5") (name "/AVDD") (class "Default")
      (node (ref "G1") (pin "AVDD") (pinfunction "AVDD_AVDD") (pintype "power_in"))
    )
    (net (code "6") (name "/CANH") (class "Default")
      (node (ref "IC2") (pin "7") (pinfunction "CANH_7") (pintype "bidirectional"))
      (node (ref "U1") (pin "7") (pinfunction "CANH_7") (pintype "bidirectional"))
      (node (ref "X1") (pin "1") (pinfunction "1_1") (pintype "passive"))
      (node (ref "X2") (pin "1") (pinfunction "1_1") (pintype "passive"))
    )
    (net (code "7") (name "/CANL") (class "Default")
      (node (ref "IC2") (pin "6") (pinfunction "CANL_6") (pintype "bidirectional"))
      (node (ref "U1") (pin "6") (pinfunction "CANL_6") (pintype "bidirectional"))
      (node (ref "X1") (pin "2") (pinfunction "2_2") (pintype "passive"))
      (node (ref "X2") (pin "2") (pinfunction "2_2") (pintype "passive"))
    )
    (net (code "8") (name "/GND4") (class "Default")
      (node (ref "G1") (pin "GND4") (pinfunction "GND4_GND4") (pintype "power_in"))
    )
    (net (code "9") (name "/PWR_POS") (class "Default")
      (node (ref "R17") (pin "2") (pinfunction "2_2") (pintype "passive"))
      (node (ref "X1") (pin "8") (pinfunction "8_8") (pintype "passive"))
      (node (ref "X2") (pin "8") (pinfunction "8_8") (pintype "passive"))
    )
    (net (code "10") (name "/U5V") (class "Default")
      (node (ref "G1") (pin "U5V") (pinfunction "U5V_U5V") (pintype "power_in"))
    )
    (net (code "11") (name "/VBAT") (class "Default")
      (node (ref "G1") (pin "VBAT") (pinfunction "VBAT_VBAT") (pintype "power_in"))
    )
    (net (code "12") (name "/VDD") (class "Default")
      (node (ref "G1") (pin "VDD") (pinfunction "VDD_VDD") (pintype "power_in"))
    )
    (net (code "13") (name "CANRX") (class "Default")
      (node (ref "G1") (pin "PB8") (pinfunction "PB8_PB8") (pintype "bidirectional"))
      (node (ref "IC2") (pin "4") (pinfunction "RXD_4") (pintype "bidirectional"))
      (node (ref "U1") (pin "4") (pinfunction "RXD_4") (pintype "output"))
    )
    (net (code "14") (name "CANTX") (class "Default")
      (node (ref "G1") (pin "PB9") (pinfunction "PB9_PB9") (pintype "bidirectional"))
      (node (ref "IC2") (pin "1") (pinfunction "TXD_1") (pintype "bidirectional"))
      (node (ref "U1") (pin "1") (pinfunction "TXD_1") (pintype "input"))
    )
    (net (code "15") (name "E_CS") (class "Default")
      (node (ref "G1") (pin "PC10") (pinfunction "PC10_PC10") (pintype "bidirectional"))
      (node (ref "JP5") (pin "4") (pinfunction "4_4") (pintype "passive"))
      (node (ref "R1") (pin "2") (pinfunction "2_2") (pintype "passive"))
    )
    (net (code "16") (name "E_LAT") (class "Default")
      (node (ref "G1") (pin "PC11") (pinfunction "PC11_PC11") (pintype "bidirectional"))
      (node (ref "JP5") (pin "5") (pinfunction "5_5") (pintype "passive"))
      (node (ref "R2") (pin "2") (pinfunction "2_2") (pintype "passive"))
    )
    (net (code "17") (name "GND") (class "Default")
      (node (ref "C1") (pin "2") (pinfunction "2_2") (pintype "passive"))
      (node (ref "C10") (pin "2") (pinfunction "2_2") (pintype "passive"))
      (node (ref "C11") (pin "2") (pinfunction "2_2") (pintype "passive"))
      (node (ref "C2") (pin "2") (pinfunction "2_2") (pintype "passive"))
      (node (ref "C3") (pin "2") (pinfunction "2_2") (pintype "passive"))
      (node (ref "C4") (pin "2") (pinfunction "2_2") (pintype "passive"))
      (node (ref "C5") (pin "2") (pinfunction "2_2") (pintype "passive"))
      (node (ref "C6") (pin "-") (pinfunction "-_-") (pintype "passive"))
      (node (ref "C7") (pin "2") (pinfunction "2_2") (pintype "passive"))
      (node (ref "C8") (pin "2") (pinfunction "2_2") (pintype "passive"))
      (node (ref "C9") (pin "2") (pinfunction "2_2") (pintype "passive"))
      (node (ref "D3") (pin "A") (pinfunction "A_A") (pintype "passive"))
      (node (ref "D4") (pin "A") (pinfunction "A_A") (pintype "passive"))
      (node (ref "G1") (pin "GND3") (pinfunction "GND3_GND3") (pintype "power_in"))
      (node (ref "G1") (pin "GND5") (pinfunction "GND5_GND5") (pintype "power_in"))
      (node (ref "G1") (pin "GND6") (pinfunction "GND6_GND6") (pintype "power_in"))
      (node (ref "G1") (pin "GND7") (pinfunction "GND7_GND7") (pintype "power_in"))
      (node (ref "G1") (pin "GND8") (pinfunction "GND8_GND8") (pintype "power_in"))
      (node (ref "IC1") (pin "2") (pinfunction "GNDSIG_2") (pintype "input"))
      (node (ref "IC1") (pin "3") (pinfunction "~{ON/OFF}_3") (pintype "input"))
      (node (ref "IC1") (pin "4") (pinfunction "GND_4") (pintype "power_in"))
      (node (ref "IC2") (pin "2") (pinfunction "VSS_2") (pintype "power_in"))
      (node (ref "J1") (pin "2") (pinfunction "2_2") (pintype "passive"))
      (node (ref "J1") (pin "3") (pinfunction "3_3") (pintype "passive"))
      (node (ref "JP1") (pin "5") (pinfunction "5_5") (pintype "passive"))
      (node (ref "JP1") (pin "6") (pinfunction "6_6") (pintype "passive"))
      (node (ref "JP10") (pin "5") (pinfunction "5_5") (pintype "passive"))
      (node (ref "JP2") (pin "5") (pinfunction "5_5") (pintype "passive"))
      (node (ref "JP2") (pin "6") (pinfunction "6_6") (pintype "passive"))
      (node (ref "JP3") (pin "5") (pinfunction "5_5") (pintype "passive"))
      (node (ref "JP3") (pin "6") (pinfunction "6_6") (pintype "passive"))
      (node (ref "JP4") (pin "5") (pinfunction "5_5") (pintype "passive"))
      (node (ref "JP4") (pin "6") (pinfunction "6_6") (pintype "passive"))
      (node (ref "JP5") (pin "8") (pinfunction "8_8") (pintype "passive"))
      (node (ref "JP6") (pin "4") (pinfunction "4_4") (pintype "passive"))
      (node (ref "JP8") (pin "5") (pinfunction "5_5") (pintype "passive"))
      (node (ref "JP9") (pin "5") (pinfunction "5_5") (pintype "passive"))
      (node (ref "Q1") (pin "2") (pinfunction "S_2") (pintype "passive"))
      (node (ref "Q10") (pin "2") (pinfunction "S_2") (pintype "passive"))
      (node (ref "Q11") (pin "2") (pinfunction "S_2") (pintype "passive"))
      (node (ref "Q12") (pin "2") (pinfunction "S_2") (pintype "passive"))
      (node (ref "Q13") (pin "2") (pinfunction "S_2") (pintype "passive"))
      (node (ref "Q14") (pin "2") (pinfunction "S_2") (pintype "passive"))
      (node (ref "Q15") (pin "2") (pinfunction "S_2") (pintype "passive"))
      (node (ref "Q16") (pin "2") (pinfunction "S_2") (pintype "passive"))
      (node (ref "Q2") (pin "2") (pinfunction "S_2") (pintype "passive"))
      (node (ref "Q3") (pin "2") (pinfunction "S_2") (pintype "passive"))
      (node (ref "Q4") (pin "2") (pinfunction "S_2") (pintype "passive"))
      (node (ref "Q5") (pin "2") (pinfunction "S_2") (pintype "passive"))
      (node (ref "Q6") (pin "2") (pinfunction "S_2") (pintype "passive"))
      (node (ref "Q7") (pin "2") (pinfunction "S_2") (pintype "passive"))
      (node (ref "Q8") (pin "2") (pinfunction "S_2") (pintype "passive"))
      (node (ref "Q9") (pin "2") (pinfunction "S_2") (pintype "passive"))
      (node (ref "R16") (pin "2") (pinfunction "2_2") (pintype "passive"))
      (node (ref "R51") (pin "1") (pinfunction "1_1") (pintype "passive"))
      (node (ref "SJ11") (pin "2") (pinfunction "2_2") (pintype "passive"))
      (node (ref "SJ12") (pin "P$2") (pinfunction "2_P$2") (pintype "passive"))
      (node (ref "SJ18") (pin "2") (pinfunction "2_2") (pintype "passive"))
      (node (ref "SJ19") (pin "P$2") (pinfunction "2_P$2") (pintype "passive"))
      (node (ref "U1") (pin "2") (pinfunction "GND_2") (pintype "power_in"))
      (node (ref "U10") (pin "3") (pinfunction "VSS_3") (pintype "power_in"))
      (node (ref "U11") (pin "13") (pinfunction "G_13") (pintype "input"))
      (node (ref "U11") (pin "8") (pinfunction "GND_8") (pintype "power_in"))
      (node (ref "U13") (pin "13") (pinfunction "G_13") (pintype "input"))
      (node (ref "U13") (pin "8") (pinfunction "GND_8") (pintype "power_in"))
      (node (ref "U2") (pin "4") (pinfunction "SD_4") (pintype "bidirectional"))
      (node (ref "U2") (pin "5") (pinfunction "GND1_5") (pintype "power_in"))
      (node (ref "U2") (pin "6") (pinfunction "GND2_6") (pintype "power_in"))
      (node (ref "U2") (pin "7") (pinfunction "GND3_7") (pintype "power_in"))
      (node (ref "U2") (pin "8") (pinfunction "GND4_8") (pintype "power_in"))
      (node (ref "U3") (pin "6") (pinfunction "INH_6") (pintype "input"))
      (node (ref "U3") (pin "8") (pinfunction "GND_8") (pintype "power_in"))
      (node (ref "U4") (pin "6") (pinfunction "INH_6") (pintype "input"))
      (node (ref "U4") (pin "8") (pinfunction "GND_8") (pintype "power_in"))
      (node (ref "U5") (pin "3") (pinfunction "VSS_3") (pintype "power_in"))
      (node (ref "U6") (pin "11") (pinfunction "V-_11") (pintype "power_in"))
      (node (ref "U7") (pin "3") (pinfunction "VSS_3") (pintype "power_in"))
      (node (ref "U8") (pin "3") (pinfunction "VSS_3") (pintype "power_in"))
      (node (ref "U9") (pin "11") (pinfunction "V-_11") (pintype "power_in"))
      (node (ref "X1") (pin "3") (pinfunction "3_3") (pintype "passive"))
      (node (ref "X1") (pin "6") (pinfunction "6_6") (pintype "passive"))
      (node (ref "X1") (pin "7") (pinfunction "7_7") (pintype "passive"))
      (node (ref "X2") (pin "3") (pinfunction "3_3") (pintype "passive"))
      (node (ref "X2") (pin "6") (pinfunction "6_6") (pintype "passive"))
      (node (ref "X2") (pin "7") (pinfunction "7_7") (pintype "passive"))
      (node (ref "X5") (pin "2") (pinfunction "2_2") (pintype "passive"))
    )
    (net (code "18") (name "I2CSCL") (class "Default")
      (node (ref "G1") (pin "PB6") (pinfunction "PB6_PB6") (pintype "bidirectional"))
      (node (ref "JP6") (pin "1") (pinfunction "1_1") (pintype "passive"))
      (node (ref "R15") (pin "2") (pinfunction "2_2") (pintype "passive"))
    )
    (net (code "19") (name "I2CSDA") (class "Default")
      (node (ref "G1") (pin "PB7") (pinfunction "PB7_PB7") (pintype "bidirectional"))
      (node (ref "JP6") (pin "2") (pinfunction "2_2") (pintype "passive"))
      (node (ref "R14") (pin "2") (pinfunction "2_2") (pintype "passive"))
    )
    (net (code "20") (name "ILAT") (class "Default")
      (node (ref "G1") (pin "PA6") (pinfunction "PA6_PA6") (pintype "bidirectional"))
      (node (ref "U3") (pin "15") (pinfunction "SH/~{LD}_15") (pintype "input"))
      (node (ref "U4") (pin "15") (pinfunction "SH/~{LD}_15") (pintype "input"))
    )
    (net (code "21") (name "MISO") (class "Default")
      (node (ref "G1") (pin "PB4") (pinfunction "PB4_PB4") (pintype "bidirectional"))
      (node (ref "JP5") (pin "1") (pinfunction "1_1") (pintype "passive"))
    )
    (net (code "22") (name "MISO2") (class "Default")
      (node (ref "G1") (pin "PC2") (pinfunction "PC2_PC2") (pintype "bidirectional"))
      (node (ref "SJ1") (pin "P$2") (pinfunction "2_P$2") (pintype "passive"))
      (node (ref "SJ6") (pin "P$2") (pinfunction "2_P$2") (pintype "passive"))
      (node (ref "U3") (pin "13") (pinfunction "QH_13") (pintype "output"))
    )
    (net (code "23") (name "MOSI") (class "Default")
      (node (ref "G1") (pin "PB5") (pinfunction "PB5_PB5") (pintype "bidirectional"))
      (node (ref "R4") (pin "1") (pinfunction "1_1") (pintype "passive"))
      (node (ref "SJ13") (pin "P$2") (pinfunction "2_P$2") (pintype "passive"))
      (node (ref "SJ3") (pin "1") (pinfunction "1_1") (pintype "passive"))
      (node (ref "U13") (pin "14") (pinfunction "SER_14") (pintype "input"))
    )
    (net (code "24") (name "Net-(D1-PadA)") (class "Default")
      (node (ref "D1") (pin "A") (pinfunction "A_A") (pintype "passive"))
      (node (ref "D2") (pin "A") (pinfunction "A_A") (pintype "passive"))
      (node (ref "JP7") (pin "4") (pinfunction "4_4") (pintype "passive"))
    )
    (net (code "25") (name "Net-(D1-PadC)") (class "Default")
      (node (ref "D1") (pin "C") (pinfunction "C_C") (pintype "passive"))
      (node (ref "D2") (pin "C") (pinfunction "C_C") (pintype "passive"))
      (node (ref "JP7") (pin "1") (pinfunction "1_1") (pintype "passive"))
    )
    (net (code "26") (name "Net-(IC1-OUT)") (class "Default")
      (node (ref "D3") (pin "C") (pinfunction "C_C") (pintype "passive"))
      (node (ref "D4") (pin "C") (pinfunction "C_C") (pintype "passive"))
      (node (ref "IC1") (pin "7") (pinfunction "OUT_7") (pintype "passive"))
      (node (ref "L1") (pin "2") (pinfunction "2_2") (pintype "passive"))
      (node (ref "U2") (pin "2") (pinfunction "VOUT_2") (pintype "bidirectional"))
    )
    (net (code "27") (name "Net-(IC2-RS)") (class "Default")
      (node (ref "IC2") (pin "8") (pinfunction "RS_8") (pintype "bidirectional"))
      (node (ref "R16") (pin "1") (pinfunction "1_1") (pintype "passive"))
      (node (ref "U1") (pin "8") (pinfunction "RS_8") (pintype "input"))
    )
    (net (code "28") (name "Net-(IC2-VREF)") (class "Default")
      (node (ref "IC2") (pin "5") (pinfunction "VREF_5") (pintype "bidirectional"))
      (node (ref "SJ5") (pin "P$2") (pinfunction "2_P$2") (pintype "passive"))
      (node (ref "U1") (pin "5") (pinfunction "VREF_5") (pintype "output"))
    )
    (net (code "29") (name "Net-(JP7-Pad3)") (class "Default")
      (node (ref "JP7") (pin "3") (pinfunction "3_3") (pintype "passive"))
      (node (ref "R17") (pin "1") (pinfunction "1_1") (pintype "passive"))
    )
    (net (code "30") (name "Net-(JP8-Pad1)") (class "Default")
      (node (ref "JP8") (pin "1") (pinfunction "1_1") (pintype "passive"))
      (node (ref "R25") (pin "2") (pinfunction "2_2") (pintype "passive"))
      (node (ref "R26") (pin "2") (pinfunction "2_2") (pintype "passive"))
      (node (ref "RN1") (pin "9") (pinfunction "9_9") (pintype "passive"))
      (node (ref "RN2") (pin "1") (pinfunction "1_1") (pintype "passive"))
      (node (ref "X3") (pin "1") (pinfunction "1_1") (pintype "passive"))
    )
    (net (code "31") (name "Net-(JP9-Pad1)") (class "Default")
      (node (ref "JP9") (pin "1") (pinfunction "1_1") (pintype "passive"))
      (node (ref "R41") (pin "2") (pinfunction "2_2") (pintype "passive"))
      (node (ref "R42") (pin "2") (pinfunction "2_2") (pintype "passive"))
      (node (ref "RN3") (pin "9") (pinfunction "9_9") (pintype "passive"))
      (node (ref "RN4") (pin "1") (pinfunction "1_1") (pintype "passive"))
      (node (ref "X4") (pin "1") (pinfunction "1_1") (pintype "passive"))
    )
    (net (code "32") (name "Net-(Q1-D)") (class "Default")
      (node (ref "Q1") (pin "3") (pinfunction "D_3") (pintype "passive"))
      (node (ref "U12") (pin "11") (pinfunction "O8_11") (pintype "open_collector"))
      (node (ref "X7") (pin "8") (pinfunction "8_8") (pintype "passive"))
    )
    (net (code "33") (name "Net-(Q1-G)") (class "Default")
      (node (ref "Q1") (pin "1") (pinfunction "G_1") (pintype "passive"))
      (node (ref "R52") (pin "2") (pinfunction "2_2") (pintype "passive"))
    )
    (net (code "34") (name "Net-(Q2-D)") (class "Default")
      (node (ref "Q2") (pin "3") (pinfunction "D_3") (pintype "passive"))
      (node (ref "U12") (pin "12") (pinfunction "O7_12") (pintype "open_collector"))
      (node (ref "X7") (pin "7") (pinfunction "7_7") (pintype "passive"))
    )
    (net (code "35") (name "Net-(Q2-G)") (class "Default")
      (node (ref "Q2") (pin "1") (pinfunction "G_1") (pintype "passive"))
      (node (ref "R53") (pin "2") (pinfunction "2_2") (pintype "passive"))
    )
    (net (code "36") (name "Net-(Q3-D)") (class "Default")
      (node (ref "Q3") (pin "3") (pinfunction "D_3") (pintype "passive"))
      (node (ref "U12") (pin "13") (pinfunction "O6_13") (pintype "open_collector"))
      (node (ref "X7") (pin "6") (pinfunction "6_6") (pintype "passive"))
    )
    (net (code "37") (name "Net-(Q3-G)") (class "Default")
      (node (ref "Q3") (pin "1") (pinfunction "G_1") (pintype "passive"))
      (node (ref "R54") (pin "2") (pinfunction "2_2") (pintype "passive"))
    )
    (net (code "38") (name "Net-(Q4-D)") (class "Default")
      (node (ref "Q4") (pin "3") (pinfunction "D_3") (pintype "passive"))
      (node (ref "U12") (pin "14") (pinfunction "O5_14") (pintype "open_collector"))
      (node (ref "X7") (pin "5") (pinfunction "5_5") (pintype "passive"))
    )
    (net (code "39") (name "Net-(Q4-G)") (class "Default")
      (node (ref "Q4") (pin "1") (pinfunction "G_1") (pintype "passive"))
      (node (ref "R55") (pin "2") (pinfunction "2_2") (pintype "passive"))
    )
    (net (code "40") (name "Net-(Q5-D)") (class "Default")
      (node (ref "Q5") (pin "3") (pinfunction "D_3") (pintype "passive"))
      (node (ref "U12") (pin "15") (pinfunction "O4_15") (pintype "open_collector"))
      (node (ref "X7") (pin "4") (pinfunction "4_4") (pintype "passive"))
    )
    (net (code "41") (name "Net-(Q5-G)") (class "Default")
      (node (ref "Q5") (pin "1") (pinfunction "G_1") (pintype "passive"))
      (node (ref "R56") (pin "2") (pinfunction "2_2") (pintype "passive"))
    )
    (net (code "42") (name "Net-(Q6-D)") (class "Default")
      (node (ref "Q6") (pin "3") (pinfunction "D_3") (pintype "passive"))
      (node (ref "U12") (pin "16") (pinfunction "O3_16") (pintype "open_collector"))
      (node (ref "X7") (pin "3") (pinfunction "3_3") (pintype "passive"))
    )
    (net (code "43") (name "Net-(Q6-G)") (class "Default")
      (node (ref "Q6") (pin "1") (pinfunction "G_1") (pintype "passive"))
      (node (ref "R57") (pin "2") (pinfunction "2_2") (pintype "passive"))
    )
    (net (code "44") (name "Net-(Q7-D)") (class "Default")
      (node (ref "Q7") (pin "3") (pinfunction "D_3") (pintype "passive"))
      (node (ref "U12") (pin "17") (pinfunction "O2_17") (pintype "open_collector"))
      (node (ref "X7") (pin "2") (pinfunction "2_2") (pintype "passive"))
    )
    (net (code "45") (name "Net-(Q7-G)") (class "Default")
      (node (ref "Q7") (pin "1") (pinfunction "G_1") (pintype "passive"))
      (node (ref "R58") (pin "2") (pinfunction "2_2") (pintype "passive"))
    )
    (net (code "46") (name "Net-(Q8-D)") (class "Default")
      (node (ref "Q8") (pin "3") (pinfunction "D_3") (pintype "passive"))
      (node (ref "U12") (pin "18") (pinfunction "O1_18") (pintype "open_collector"))
      (node (ref "X7") (pin "1") (pinfunction "1_1") (pintype "passive"))
    )
    (net (code "47") (name "Net-(Q8-G)") (class "Default")
      (node (ref "Q8") (pin "1") (pinfunction "G_1") (pintype "passive"))
      (node (ref "R59") (pin "2") (pinfunction "2_2") (pintype "passive"))
    )
    (net (code "48") (name "Net-(Q9-D)") (class "Default")
      (node (ref "Q9") (pin "3") (pinfunction "D_3") (pintype "passive"))
      (node (ref "U14") (pin "11") (pinfunction "O8_11") (pintype "open_collector"))
      (node (ref "X8") (pin "8") (pinfunction "8_8") (pintype "passive"))
    )
    (net (code "49") (name "Net-(Q9-G)") (class "Default")
      (node (ref "Q9") (pin "1") (pinfunction "G_1") (pintype "passive"))
      (node (ref "R60") (pin "2") (pinfunction "2_2") (pintype "passive"))
    )
    (net (code "50") (name "Net-(Q10-D)") (class "Default")
      (node (ref "Q10") (pin "3") (pinfunction "D_3") (pintype "passive"))
      (node (ref "U14") (pin "12") (pinfunction "O7_12") (pintype "open_collector"))
      (node (ref "X8") (pin "7") (pinfunction "7_7") (pintype "passive"))
    )
    (net (code "51") (name "Net-(Q10-G)") (class "Default")
      (node (ref "Q10") (pin "1") (pinfunction "G_1") (pintype "passive"))
      (node (ref "R61") (pin "2") (pinfunction "2_2") (pintype "passive"))
    )
    (net (code "52") (name "Net-(Q11-D)") (class "Default")
      (node (ref "Q11") (pin "3") (pinfunction "D_3") (pintype "passive"))
      (node (ref "U14") (pin "13") (pinfunction "O6_13") (pintype "open_collector"))
      (node (ref "X8") (pin "6") (pinfunction "6_6") (pintype "passive"))
    )
    (net (code "53") (name "Net-(Q11-G)") (class "Default")
      (node (ref "Q11") (pin "1") (pinfunction "G_1") (pintype "passive"))
      (node (ref "R62") (pin "2") (pinfunction "2_2") (pintype "passive"))
    )
    (net (code "54") (name "Net-(Q12-D)") (class "Default")
      (node (ref "Q12") (pin "3") (pinfunction "D_3") (pintype "passive"))
      (node (ref "U14") (pin "14") (pinfunction "O5_14") (pintype "open_collector"))
      (node (ref "X8") (pin "5") (pinfunction "5_5") (pintype "passive"))
    )
    (net (code "55") (name "Net-(Q12-G)") (class "Default")
      (node (ref "Q12") (pin "1") (pinfunction "G_1") (pintype "passive"))
      (node (ref "R63") (pin "2") (pinfunction "2_2") (pintype "passive"))
    )
    (net (code "56") (name "Net-(Q13-D)") (class "Default")
      (node (ref "Q13") (pin "3") (pinfunction "D_3") (pintype "passive"))
      (node (ref "U14") (pin "15") (pinfunction "O4_15") (pintype "open_collector"))
      (node (ref "X8") (pin "4") (pinfunction "4_4") (pintype "passive"))
    )
    (net (code "57") (name "Net-(Q13-G)") (class "Default")
      (node (ref "Q13") (pin "1") (pinfunction "G_1") (pintype "passive"))
      (node (ref "R64") (pin "2") (pinfunction "2_2") (pintype "passive"))
    )
    (net (code "58") (name "Net-(Q14-D)") (class "Default")
      (node (ref "Q14") (pin "3") (pinfunction "D_3") (pintype "passive"))
      (node (ref "U14") (pin "16") (pinfunction "O3_16") (pintype "open_collector"))
      (node (ref "X8") (pin "3") (pinfunction "3_3") (pintype "passive"))
    )
    (net (code "59") (name "Net-(Q14-G)") (class "Default")
      (node (ref "Q14") (pin "1") (pinfunction "G_1") (pintype "passive"))
      (node (ref "R65") (pin "2") (pinfunction "2_2") (pintype "passive"))
    )
    (net (code "60") (name "Net-(Q15-D)") (class "Default")
      (node (ref "Q15") (pin "3") (pinfunction "D_3") (pintype "passive"))
      (node (ref "U14") (pin "17") (pinfunction "O2_17") (pintype "open_collector"))
      (node (ref "X8") (pin "2") (pinfunction "2_2") (pintype "passive"))
    )
    (net (code "61") (name "Net-(Q15-G)") (class "Default")
      (node (ref "Q15") (pin "1") (pinfunction "G_1") (pintype "passive"))
      (node (ref "R66") (pin "2") (pinfunction "2_2") (pintype "passive"))
    )
    (net (code "62") (name "Net-(Q16-D)") (class "Default")
      (node (ref "Q16") (pin "3") (pinfunction "D_3") (pintype "passive"))
      (node (ref "U14") (pin "18") (pinfunction "O1_18") (pintype "open_collector"))
      (node (ref "X8") (pin "1") (pinfunction "1_1") (pintype "passive"))
    )
    (net (code "63") (name "Net-(Q16-G)") (class "Default")
      (node (ref "Q16") (pin "1") (pinfunction "G_1") (pintype "passive"))
      (node (ref "R67") (pin "2") (pinfunction "2_2") (pintype "passive"))
    )
    (net (code "64") (name "Net-(RN2A-2)") (class "Default")
      (node (ref "R25") (pin "1") (pinfunction "1_1") (pintype "passive"))
      (node (ref "RN2") (pin "16") (pinfunction "2_16") (pintype "passive"))
      (node (ref "U3") (pin "14") (pinfunction "H_14") (pintype "input"))
    )
    (net (code "65") (name "Net-(RN2B-1)") (class "Default")
      (node (ref "JP8") (pin "2") (pinfunction "2_2") (pintype "passive"))
      (node (ref "R24") (pin "2") (pinfunction "2_2") (pintype "passive"))
      (node (ref "R27") (pin "2") (pinfunction "2_2") (pintype "passive"))
      (node (ref "RN1") (pin "8") (pinfunction "8_8") (pintype "passive"))
      (node (ref "RN2") (pin "2") (pinfunction "1_2") (pintype "passive"))
      (node (ref "X3") (pin "2") (pinfunction "2_2") (pintype "passive"))
    )
    (net (code "66") (name "Net-(RN2B-2)") (class "Default")
      (node (ref "R24") (pin "1") (pinfunction "1_1") (pintype "passive"))
      (node (ref "RN2") (pin "15") (pinfunction "2_15") (pintype "passive"))
      (node (ref "U3") (pin "12") (pinfunction "G_12") (pintype "input"))
    )
    (net (code "67") (name "Net-(RN2C-1)") (class "Default")
      (node (ref "JP8") (pin "3") (pinfunction "3_3") (pintype "passive"))
      (node (ref "R23") (pin "2") (pinfunction "2_2") (pintype "passive"))
      (node (ref "R28") (pin "2") (pinfunction "2_2") (pintype "passive"))
      (node (ref "RN1") (pin "7") (pinfunction "7_7") (pintype "passive"))
      (node (ref "RN2") (pin "3") (pinfunction "1_3") (pintype "passive"))
      (node (ref "X3") (pin "3") (pinfunction "3_3") (pintype "passive"))
    )
    (net (code "68") (name "Net-(RN2C-2)") (class "Default")
      (node (ref "R23") (pin "1") (pinfunction "1_1") (pintype "passive"))
      (node (ref "RN2") (pin "14") (pinfunction "2_14") (pintype "passive"))
      (node (ref "U3") (pin "11") (pinfunction "F_11") (pintype "input"))
    )
    (net (code "69") (name "Net-(RN2D-1)") (class "Default")
      (node (ref "JP8") (pin "4") (pinfunction "4_4") (pintype "passive"))
      (node (ref "R22") (pin "2") (pinfunction "2_2") (pintype "passive"))
      (node (ref "R29") (pin "2") (pinfunction "2_2") (pintype "passive"))
      (node (ref "RN1") (pin "6") (pinfunction "6_6") (pintype "passive"))
      (node (ref "RN2") (pin "4") (pinfunction "1_4") (pintype "passive"))
      (node (ref "X3") (pin "4") (pinfunction "4_4") (pintype "passive"))
    )
    (net (code "70") (name "Net-(RN2D-2)") (class "Default")
      (node (ref "R22") (pin "1") (pinfunction "1_1") (pintype "passive"))
      (node (ref "RN2") (pin "13") (pinfunction "2_13") (pintype "passive"))
      (node (ref "U3") (pin "10") (pinfunction "E_10") (pintype "input"))
    )
    (net (code "71") (name "Net-(RN2E-1)") (class "Default")
      (node (ref "JP8") (pin "7") (pinfunction "7_7") (pintype "passive"))
      (node (ref "R21") (pin "2") (pinfunction "2_2") (pintype "passive"))
      (node (ref "R30") (pin "2") (pinfunction "2_2") (pintype "passive"))
      (node (ref "RN1") (pin "5") (pinfunction "5_5") (pintype "passive"))
      (node (ref "RN2") (pin "5") (pinfunction "1_5") (pintype "passive"))
      (node (ref "X3") (pin "5") (pinfunction "5_5") (pintype "passive"))
    )
    (net (code "72") (name "Net-(RN2E-2)") (class "Default")
      (node (ref "R21") (pin "1") (pinfunction "1_1") (pintype "passive"))
      (node (ref "RN2") (pin "12") (pinfunction "2_12") (pintype "passive"))
      (node (ref "U3") (pin "5") (pinfunction "D_5") (pintype "input"))
    )
    (net (code "73") (name "Net-(RN2F-1)") (class "Default")
      (node (ref "JP8") (pin "8") (pinfunction "8_8") (pintype "passive"))
      (node (ref "R20") (pin "2") (pinfunction "2_2") (pintype "passive"))
      (node (ref "R31") (pin "2") (pinfunction "2_2") (pintype "passive"))
      (node (ref "RN1") (pin "4") (pinfunction "4_4") (pintype "passive"))
      (node (ref "RN2") (pin "6") (pinfunction "1_6") (pintype "passive"))
      (node (ref "X3") (pin "6") (pinfunction "6_6") (pintype "passive"))
    )
    (net (code "74") (name "Net-(RN2F-2)") (class "Default")
      (node (ref "R20") (pin "1") (pinfunction "1_1") (pintype "passive"))
      (node (ref "RN2") (pin "11") (pinfunction "2_11") (pintype "passive"))
      (node (ref "U3") (pin "4") (pinfunction "C_4") (pintype "input"))
    )
    (net (code "75") (name "Net-(RN2G-1)") (class "Default")
      (node (ref "JP8") (pin "9") (pinfunction "9_9") (pintype "passive"))
      (node (ref "R19") (pin "2") (pinfunction "2_2") (pintype "passive"))
      (node (ref "R32") (pin "2") (pinfunction "2_2") (pintype "passive"))
      (node (ref "RN1") (pin "3") (pinfunction "3_3") (pintype "passive"))
      (node (ref "RN2") (pin "7") (pinfunction "1_7") (pintype "passive"))
      (node (ref "X3") (pin "7") (pinfunction "7_7") (pintype "passive"))
    )
    (net (code "76") (name "Net-(RN2G-2)") (class "Default")
      (node (ref "R19") (pin "1") (pinfunction "1_1") (pintype "passive"))
      (node (ref "RN2") (pin "10") (pinfunction "2_10") (pintype "passive"))
      (node (ref "U3") (pin "3") (pinfunction "B_3") (pintype "input"))
    )
    (net (code "77") (name "Net-(RN2H-1)") (class "Default")
      (node (ref "JP8") (pin "10") (pinfunction "10_10") (pintype "passive"))
      (node (ref "R18") (pin "2") (pinfunction "2_2") (pintype "passive"))
      (node (ref "R33") (pin "2") (pinfunction "2_2") (pintype "passive"))
      (node (ref "RN1") (pin "2") (pinfunction "2_2") (pintype "passive"))
      (node (ref "RN2") (pin "8") (pinfunction "1_8") (pintype "passive"))
      (node (ref "X3") (pin "8") (pinfunction "8_8") (pintype "passive"))
    )
    (net (code "78") (name "Net-(RN2H-2)") (class "Default")
      (node (ref "R18") (pin "1") (pinfunction "1_1") (pintype "passive"))
      (node (ref "RN2") (pin "9") (pinfunction "2_9") (pintype "passive"))
      (node (ref "U3") (pin "2") (pinfunction "A_2") (pintype "input"))
    )
    (net (code "79") (name "Net-(RN4A-2)") (class "Default")
      (node (ref "R41") (pin "1") (pinfunction "1_1") (pintype "passive"))
      (node (ref "RN4") (pin "16") (pinfunction "2_16") (pintype "passive"))
      (node (ref "U4") (pin "14") (pinfunction "H_14") (pintype "input"))
    )
    (net (code "80") (name "Net-(RN4B-1)") (class "Default")
      (node (ref "JP9") (pin "2") (pinfunction "2_2") (pintype "passive"))
      (node (ref "R40") (pin "2") (pinfunction "2_2") (pintype "passive"))
      (node (ref "R43") (pin "2") (pinfunction "2_2") (pintype "passive"))
      (node (ref "RN3") (pin "8") (pinfunction "8_8") (pintype "passive"))
      (node (ref "RN4") (pin "2") (pinfunction "1_2") (pintype "passive"))
      (node (ref "X4") (pin "2") (pinfunction "2_2") (pintype "passive"))
    )
    (net (code "81") (name "Net-(RN4B-2)") (class "Default")
      (node (ref "R40") (pin "1") (pinfunction "1_1") (pintype "passive"))
      (node (ref "RN4") (pin "15") (pinfunction "2_15") (pintype "passive"))
      (node (ref "U4") (pin "12") (pinfunction "G_12") (pintype "input"))
    )
    (net (code "82") (name "Net-(RN4C-1)") (class "Default")
      (node (ref "JP9") (pin "3") (pinfunction "3_3") (pintype "passive"))
      (node (ref "R39") (pin "2") (pinfunction "2_2") (pintype "passive"))
      (node (ref "R44") (pin "2") (pinfunction "2_2") (pintype "passive"))
      (node (ref "RN3") (pin "7") (pinfunction "7_7") (pintype "passive"))
      (node (ref "RN4") (pin "3") (pinfunction "1_3") (pintype "passive"))
      (node (ref "X4") (pin "3") (pinfunction "3_3") (pintype "passive"))
    )
    (net (code "83") (name "Net-(RN4C-2)") (class "Default")
      (node (ref "R39") (pin "1") (pinfunction "1_1") (pintype "passive"))
      (node (ref "RN4") (pin "14") (pinfunction "2_14") (pintype "passive"))
      (node (ref "U4") (pin "11") (pinfunction "F_11") (pintype "input"))
    )
    (net (code "84") (name "Net-(RN4D-1)") (class "Default")
      (node (ref "JP9") (pin "4") (pinfunction "4_4") (pintype "passive"))
      (node (ref "R38") (pin "2") (pinfunction "2_2") (pintype "passive"))
      (node (ref "R45") (pin "2") (pinfunction "2_2") (pintype "passive"))
      (node (ref "RN3") (pin "6") (pinfunction "6_6") (pintype "passive"))
      (node (ref "RN4") (pin "4") (pinfunction "1_4") (pintype "passive"))
      (node (ref "X4") (pin "4") (pinfunction "4_4") (pintype "passive"))
    )
    (net (code "85") (name "Net-(RN4D-2)") (class "Default")
      (node (ref "R38") (pin "1") (pinfunction "1_1") (pintype "passive"))
      (node (ref "RN4") (pin "13") (pinfunction "2_13") (pintype "passive"))
      (node (ref "U4") (pin "10") (pinfunction "E_10") (pintype "input"))
    )
    (net (code "86") (name "Net-(RN4E-1)") (class "Default")
      (node (ref "JP9") (pin "7") (pinfunction "7_7") (pintype "passive"))
      (node (ref "R37") (pin "2") (pinfunction "2_2") (pintype "passive"))
      (node (ref "R46") (pin "2") (pinfunction "2_2") (pintype "passive"))
      (node (ref "RN3") (pin "5") (pinfunction "5_5") (pintype "passive"))
      (node (ref "RN4") (pin "5") (pinfunction "1_5") (pintype "passive"))
      (node (ref "X4") (pin "5") (pinfunction "5_5") (pintype "passive"))
    )
    (net (code "87") (name "Net-(RN4E-2)") (class "Default")
      (node (ref "R37") (pin "1") (pinfunction "1_1") (pintype "passive"))
      (node (ref "RN4") (pin "12") (pinfunction "2_12") (pintype "passive"))
      (node (ref "U4") (pin "5") (pinfunction "D_5") (pintype "input"))
    )
    (net (code "88") (name "Net-(RN4F-1)") (class "Default")
      (node (ref "JP9") (pin "8") (pinfunction "8_8") (pintype "passive"))
      (node (ref "R36") (pin "2") (pinfunction "2_2") (pintype "passive"))
      (node (ref "R47") (pin "2") (pinfunction "2_2") (pintype "passive"))
      (node (ref "RN3") (pin "4") (pinfunction "4_4") (pintype "passive"))
      (node (ref "RN4") (pin "6") (pinfunction "1_6") (pintype "passive"))
      (node (ref "X4") (pin "6") (pinfunction "6_6") (pintype "passive"))
    )
    (net (code "89") (name "Net-(RN4F-2)") (class "Default")
      (node (ref "R36") (pin "1") (pinfunction "1_1") (pintype "passive"))
      (node (ref "RN4") (pin "11") (pinfunction "2_11") (pintype "passive"))
      (node (ref "U4") (pin "4") (pinfunction "C_4") (pintype "input"))
    )
    (net (code "90") (name "Net-(RN4G-1)") (class "Default")
      (node (ref "JP9") (pin "9") (pinfunction "9_9") (pintype "passive"))
      (node (ref "R35") (pin "2") (pinfunction "2_2") (pintype "passive"))
      (node (ref "R48") (pin "2") (pinfunction "2_2") (pintype "passive"))
      (node (ref "RN3") (pin "3") (pinfunction "3_3") (pintype "passive"))
      (node (ref "RN4") (pin "7") (pinfunction "1_7") (pintype "passive"))
      (node (ref "X4") (pin "7") (pinfunction "7_7") (pintype "passive"))
    )
    (net (code "91") (name "Net-(RN4G-2)") (class "Default")
      (node (ref "R35") (pin "1") (pinfunction "1_1") (pintype "passive"))
      (node (ref "RN4") (pin "10") (pinfunction "2_10") (pintype "passive"))
      (node (ref "U4") (pin "3") (pinfunction "B_3") (pintype "input"))
    )
    (net (code "92") (name "Net-(RN4H-1)") (class "Default")
      (node (ref "JP9") (pin "10") (pinfunction "10_10") (pintype "passive"))
      (node (ref "R34") (pin "2") (pinfunction "2_2") (pintype "passive"))
      (node (ref "R49") (pin "2") (pinfunction "2_2") (pintype "passive"))
      (node (ref "RN3") (pin "2") (pinfunction "2_2") (pintype "passive"))
      (node (ref "RN4") (pin "8") (pinfunction "1_8") (pintype "passive"))
      (node (ref "X4") (pin "8") (pinfunction "8_8") (pintype "passive"))
    )
    (net (code "93") (name "Net-(RN4H-2)") (class "Default")
      (node (ref "R34") (pin "1") (pinfunction "1_1") (pintype "passive"))
      (node (ref "RN4") (pin "9") (pinfunction "2_9") (pintype "passive"))
      (node (ref "U4") (pin "2") (pinfunction "A_2") (pintype "input"))
    )
    (net (code "94") (name "Net-(SJ1-1)") (class "Default")
      (node (ref "G1") (pin "PB14") (pinfunction "PB14_PB14") (pintype "bidirectional"))
      (node (ref "SJ1") (pin "P$1") (pinfunction "1_P$1") (pintype "passive"))
    )
    (net (code "95") (name "Net-(SJ2-1)") (class "Default")
      (node (ref "G1") (pin "VIN2") (pinfunction "VIN2_VIN2") (pintype "power_in"))
      (node (ref "SJ2") (pin "P$1") (pinfunction "1_P$1") (pintype "passive"))
    )
    (net (code "96") (name "Net-(SJ4-2)") (class "Default")
      (node (ref "JP5") (pin "2") (pinfunction "2_2") (pintype "passive"))
      (node (ref "SJ3") (pin "2") (pinfunction "2_2") (pintype "passive"))
      (node (ref "SJ4") (pin "P$2") (pinfunction "2_P$2") (pintype "passive"))
    )
    (net (code "97") (name "Net-(SJ7-1)") (class "Default")
      (node (ref "SJ11") (pin "1") (pinfunction "1_1") (pintype "passive"))
      (node (ref "SJ7") (pin "P$1") (pinfunction "1_P$1") (pintype "passive"))
      (node (ref "SJ9") (pin "P$1") (pinfunction "1_P$1") (pintype "passive"))
      (node (ref "U12") (pin "9") (pinfunction "GND_9") (pintype "power_in"))
    )
    (net (code "98") (name "Net-(SJ10-1)") (class "Default")
      (node (ref "SJ10") (pin "P$1") (pinfunction "1_P$1") (pintype "passive"))
      (node (ref "SJ12") (pin "P$1") (pinfunction "1_P$1") (pintype "passive"))
      (node (ref "SJ8") (pin "P$1") (pinfunction "1_P$1") (pintype "passive"))
      (node (ref "U12") (pin "10") (pinfunction "CD+_10") (pintype "passive"))
    )
    (net (code "99") (name "Net-(SJ14-1)") (class "Default")
      (node (ref "SJ14") (pin "P$1") (pinfunction "1_P$1") (pintype "passive"))
      (node (ref "SJ16") (pin "P$1") (pinfunction "1_P$1") (pintype "passive"))
      (node (ref "SJ18") (pin "1") (pinfunction "1_1") (pintype "passive"))
      (node (ref "U14") (pin "9") (pinfunction "GND_9") (pintype "power_in"))
    )
    (net (code "100") (name "Net-(SJ15-1)") (class "Default")
      (node (ref "SJ15") (pin "P$1") (pinfunction "1_P$1") (pintype "passive"))
      (node (ref "SJ17") (pin "P$1") (pinfunction "1_P$1") (pintype "passive"))
      (node (ref "SJ19") (pin "P$1") (pinfunction "1_P$1") (pintype "passive"))
      (node (ref "U14") (pin "10") (pinfunction "CD+_10") (pintype "passive"))
    )
    (net (code "101") (name "Net-(SJ20-2)") (class "Default")
      (node (ref "G1") (pin "PB13") (pinfunction "PB13_PB13") (pintype "bidirectional"))
      (node (ref "SJ20") (pin "P$2") (pinfunction "2_P$2") (pintype "passive"))
    )
    (net (code "102") (name "Net-(U5A-O)") (class "Default")
      (node (ref "JP10") (pin "1") (pinfunction "1_1") (pintype "passive"))
      (node (ref "U5") (pin "7") (pinfunction "O_7") (pintype "output"))
      (node (ref "U6") (pin "7") (pinfunction "OUT_7") (pintype "output"))
      (node (ref "X6") (pin "1") (pinfunction "1_1") (pintype "passive"))
    )
    (net (code "103") (name "Net-(U5B-O)") (class "Default")
      (node (ref "JP10") (pin "2") (pinfunction "2_2") (pintype "passive"))
      (node (ref "U5") (pin "5") (pinfunction "O_5") (pintype "output"))
      (node (ref "U6") (pin "8") (pinfunction "OUT_8") (pintype "output"))
      (node (ref "X6") (pin "2") (pinfunction "2_2") (pintype "passive"))
    )
    (net (code "104") (name "Net-(U6A--IN)") (class "Default")
      (node (ref "R50") (pin "1") (pinfunction "1_1") (pintype "passive"))
      (node (ref "R51") (pin "2") (pinfunction "2_2") (pintype "passive"))
      (node (ref "U6") (pin "13") (pinfunction "-IN_13") (pintype "input"))
      (node (ref "U6") (pin "2") (pinfunction "-IN_2") (pintype "input"))
      (node (ref "U6") (pin "6") (pinfunction "-IN_6") (pintype "input"))
      (node (ref "U6") (pin "9") (pinfunction "-IN_9") (pintype "input"))
      (node (ref "U9") (pin "13") (pinfunction "-IN_13") (pintype "input"))
      (node (ref "U9") (pin "2") (pinfunction "-IN_2") (pintype "input"))
      (node (ref "U9") (pin "6") (pinfunction "-IN_6") (pintype "input"))
      (node (ref "U9") (pin "9") (pinfunction "-IN_9") (pintype "input"))
    )
    (net (code "105") (name "Net-(U6A-OUT)") (class "Default")
      (node (ref "JP10") (pin "3") (pinfunction "3_3") (pintype "passive"))
      (node (ref "U6") (pin "1") (pinfunction "OUT_1") (pintype "output"))
      (node (ref "U7") (pin "5") (pinfunction "O_5") (pintype "output"))
      (node (ref "X6") (pin "3") (pinfunction "3_3") (pintype "passive"))
    )
    (net (code "106") (name "Net-(U6D-OUT)") (class "Default")
      (node (ref "JP10") (pin "4") (pinfunction "4_4") (pintype "passive"))
      (node (ref "U6") (pin "14") (pinfunction "OUT_14") (pintype "output"))
      (node (ref "U7") (pin "7") (pinfunction "O_7") (pintype "output"))
      (node (ref "X6") (pin "4") (pinfunction "4_4") (pintype "passive"))
    )
    (net (code "107") (name "Net-(U8A-O)") (class "Default")
      (node (ref "JP10") (pin "7") (pinfunction "7_7") (pintype "passive"))
      (node (ref "U8") (pin "7") (pinfunction "O_7") (pintype "output"))
      (node (ref "U9") (pin "7") (pinfunction "OUT_7") (pintype "output"))
      (node (ref "X6") (pin "5") (pinfunction "5_5") (pintype "passive"))
    )
    (net (code "108") (name "Net-(U8B-O)") (class "Default")
      (node (ref "JP10") (pin "8") (pinfunction "8_8") (pintype "passive"))
      (node (ref "U8") (pin "5") (pinfunction "O_5") (pintype "output"))
      (node (ref "U9") (pin "8") (pinfunction "OUT_8") (pintype "output"))
      (node (ref "X6") (pin "6") (pinfunction "6_6") (pintype "passive"))
    )
    (net (code "109") (name "Net-(U10A-O)") (class "Default")
      (node (ref "JP10") (pin "10") (pinfunction "10_10") (pintype "passive"))
      (node (ref "U10") (pin "7") (pinfunction "O_7") (pintype "output"))
      (node (ref "U9") (pin "14") (pinfunction "OUT_14") (pintype "output"))
      (node (ref "X6") (pin "8") (pinfunction "8_8") (pintype "passive"))
    )
    (net (code "110") (name "Net-(U10B-O)") (class "Default")
      (node (ref "JP10") (pin "9") (pinfunction "9_9") (pintype "passive"))
      (node (ref "U10") (pin "5") (pinfunction "O_5") (pintype "output"))
      (node (ref "U9") (pin "1") (pinfunction "OUT_1") (pintype "output"))
      (node (ref "X6") (pin "7") (pinfunction "7_7") (pintype "passive"))
    )
    (net (code "111") (name "Net-(U11A-QA)") (class "Default")
      (node (ref "R59") (pin "1") (pinfunction "1_1") (pintype "passive"))
      (node (ref "U11") (pin "15") (pinfunction "QA_15") (pintype "tri_state"))
      (node (ref "U12") (pin "1") (pinfunction "I1_1") (pintype "input"))
    )
    (net (code "112") (name "Net-(U11A-QB)") (class "Default")
      (node (ref "R58") (pin "1") (pinfunction "1_1") (pintype "passive"))
      (node (ref "U11") (pin "1") (pinfunction "QB_1") (pintype "tri_state"))
      (node (ref "U12") (pin "2") (pinfunction "I2_2") (pintype "input"))
    )
    (net (code "113") (name "Net-(U11A-QC)") (class "Default")
      (node (ref "R57") (pin "1") (pinfunction "1_1") (pintype "passive"))
      (node (ref "U11") (pin "2") (pinfunction "QC_2") (pintype "tri_state"))
      (node (ref "U12") (pin "3") (pinfunction "I3_3") (pintype "input"))
    )
    (net (code "114") (name "Net-(U11A-QD)") (class "Default")
      (node (ref "R56") (pin "1") (pinfunction "1_1") (pintype "passive"))
      (node (ref "U11") (pin "3") (pinfunction "QD_3") (pintype "tri_state"))
      (node (ref "U12") (pin "4") (pinfunction "I4_4") (pintype "input"))
    )
    (net (code "115") (name "Net-(U11A-QE)") (class "Default")
      (node (ref "R55") (pin "1") (pinfunction "1_1") (pintype "passive"))
      (node (ref "U11") (pin "4") (pinfunction "QE_4") (pintype "tri_state"))
      (node (ref "U12") (pin "5") (pinfunction "I5_5") (pintype "input"))
    )
    (net (code "116") (name "Net-(U11A-QF)") (class "Default")
      (node (ref "R54") (pin "1") (pinfunction "1_1") (pintype "passive"))
      (node (ref "U11") (pin "5") (pinfunction "QF_5") (pintype "tri_state"))
      (node (ref "U12") (pin "6") (pinfunction "I6_6") (pintype "input"))
    )
    (net (code "117") (name "Net-(U11A-QG)") (class "Default")
      (node (ref "R53") (pin "1") (pinfunction "1_1") (pintype "passive"))
      (node (ref "U11") (pin "6") (pinfunction "QG_6") (pintype "tri_state"))
      (node (ref "U12") (pin "7") (pinfunction "I7_7") (pintype "input"))
    )
    (net (code "118") (name "Net-(U11A-QH)") (class "Default")
      (node (ref "R52") (pin "1") (pinfunction "1_1") (pintype "passive"))
      (node (ref "U11") (pin "7") (pinfunction "QH_7") (pintype "tri_state"))
      (node (ref "U12") (pin "8") (pinfunction "I8_8") (pintype "input"))
    )
    (net (code "119") (name "Net-(U13A-QA)") (class "Default")
      (node (ref "R67") (pin "1") (pinfunction "1_1") (pintype "passive"))
      (node (ref "U13") (pin "15") (pinfunction "QA_15") (pintype "tri_state"))
      (node (ref "U14") (pin "1") (pinfunction "I1_1") (pintype "input"))
    )
    (net (code "120") (name "Net-(U13A-QB)") (class "Default")
      (node (ref "R66") (pin "1") (pinfunction "1_1") (pintype "passive"))
      (node (ref "U13") (pin "1") (pinfunction "QB_1") (pintype "tri_state"))
      (node (ref "U14") (pin "2") (pinfunction "I2_2") (pintype "input"))
    )
    (net (code "121") (name "Net-(U13A-QC)") (class "Default")
      (node (ref "R65") (pin "1") (pinfunction "1_1") (pintype "passive"))
      (node (ref "U13") (pin "2") (pinfunction "QC_2") (pintype "tri_state"))
      (node (ref "U14") (pin "3") (pinfunction "I3_3") (pintype "input"))
    )
    (net (code "122") (name "Net-(U13A-QD)") (class "Default")
      (node (ref "R64") (pin "1") (pinfunction "1_1") (pintype "passive"))
      (node (ref "U13") (pin "3") (pinfunction "QD_3") (pintype "tri_state"))
      (node (ref "U14") (pin "4") (pinfunction "I4_4") (pintype "input"))
    )
    (net (code "123") (name "Net-(U13A-QE)") (class "Default")
      (node (ref "R63") (pin "1") (pinfunction "1_1") (pintype "passive"))
      (node (ref "U13") (pin "4") (pinfunction "QE_4") (pintype "tri_state"))
      (node (ref "U14") (pin "5") (pinfunction "I5_5") (pintype "input"))
    )
    (net (code "124") (name "Net-(U13A-QF)") (class "Default")
      (node (ref "R62") (pin "1") (pinfunction "1_1") (pintype "passive"))
      (node (ref "U13") (pin "5") (pinfunction "QF_5") (pintype "tri_state"))
      (node (ref "U14") (pin "6") (pinfunction "I6_6") (pintype "input"))
    )
    (net (code "125") (name "Net-(U13A-QG)") (class "Default")
      (node (ref "R61") (pin "1") (pinfunction "1_1") (pintype "passive"))
      (node (ref "U13") (pin "6") (pinfunction "QG_6") (pintype "tri_state"))
      (node (ref "U14") (pin "7") (pinfunction "I7_7") (pintype "input"))
    )
    (net (code "126") (name "Net-(U13A-QH)") (class "Default")
      (node (ref "R60") (pin "1") (pinfunction "1_1") (pintype "passive"))
      (node (ref "U13") (pin "7") (pinfunction "QH_7") (pintype "tri_state"))
      (node (ref "U14") (pin "8") (pinfunction "I8_8") (pintype "input"))
    )
    (net (code "127") (name "Net-(X1-Pad4)") (class "Default")
      (node (ref "X1") (pin "4") (pinfunction "4_4") (pintype "passive"))
      (node (ref "X2") (pin "4") (pinfunction "4_4") (pintype "passive"))
    )
    (net (code "128") (name "Net-(X1-Pad5)") (class "Default")
      (node (ref "X1") (pin "5") (pinfunction "5_5") (pintype "passive"))
      (node (ref "X2") (pin "5") (pinfunction "5_5") (pintype "passive"))
    )
    (net (code "129") (name "OLAT") (class "Default")
      (node (ref "G1") (pin "PA8") (pinfunction "PA8_PA8") (pintype "bidirectional"))
      (node (ref "R3") (pin "1") (pinfunction "1_1") (pintype "passive"))
      (node (ref "U11") (pin "12") (pinfunction "RCK_12") (pintype "input"))
      (node (ref "U13") (pin "12") (pinfunction "RCK_12") (pintype "input"))
    )
    (net (code "130") (name "SCK") (class "Default")
      (node (ref "G1") (pin "PB3") (pinfunction "PB3_PB3") (pintype "bidirectional"))
      (node (ref "JP5") (pin "3") (pinfunction "3_3") (pintype "passive"))
      (node (ref "R5") (pin "1") (pinfunction "1_1") (pintype "passive"))
      (node (ref "U11") (pin "11") (pinfunction "SCK_11") (pintype "input"))
      (node (ref "U13") (pin "11") (pinfunction "SCK_11") (pintype "input"))
    )
    (net (code "131") (name "SCK2") (class "Default")
      (node (ref "G1") (pin "PB10") (pinfunction "PB10_PB10") (pintype "bidirectional"))
      (node (ref "SJ20") (pin "P$1") (pinfunction "1_P$1") (pintype "passive"))
      (node (ref "U3") (pin "7") (pinfunction "CLK_7") (pintype "input"))
      (node (ref "U4") (pin "7") (pinfunction "CLK_7") (pintype "input"))
    )
    (net (code "132") (name "SLNK1") (class "Default")
      (node (ref "SJ13") (pin "P$1") (pinfunction "1_P$1") (pintype "passive"))
      (node (ref "U11") (pin "14") (pinfunction "SER_14") (pintype "input"))
      (node (ref "U13") (pin "9") (pinfunction "QH*_9") (pintype "tri_state"))
    )
    (net (code "133") (name "SLNK2") (class "Default")
      (node (ref "SJ4") (pin "P$1") (pinfunction "1_P$1") (pintype "passive"))
      (node (ref "U11") (pin "9") (pinfunction "QH*_9") (pintype "tri_state"))
    )
    (net (code "134") (name "SLNK3") (class "Default")
      (node (ref "SJ6") (pin "P$1") (pinfunction "1_P$1") (pintype "passive"))
      (node (ref "U3") (pin "1") (pinfunction "SER_1") (pintype "input"))
      (node (ref "U4") (pin "13") (pinfunction "QH_13") (pintype "output"))
    )
    (net (code "135") (name "SRV1") (class "Default")
      (node (ref "G1") (pin "PC9") (pinfunction "PC9_PC9") (pintype "bidirectional"))
      (node (ref "JP4") (pin "2") (pinfunction "2_2") (pintype "passive"))
      (node (ref "R13") (pin "2") (pinfunction "2_2") (pintype "passive"))
    )
    (net (code "136") (name "SRV2") (class "Default")
      (node (ref "G1") (pin "PC7") (pinfunction "PC7_PC7") (pintype "bidirectional"))
      (node (ref "JP4") (pin "1") (pinfunction "1_1") (pintype "passive"))
      (node (ref "R12") (pin "2") (pinfunction "2_2") (pintype "passive"))
    )
    (net (code "137") (name "SRV3") (class "Default")
      (node (ref "G1") (pin "PC8") (pinfunction "PC8_PC8") (pintype "bidirectional"))
      (node (ref "JP3") (pin "2") (pinfunction "2_2") (pintype "passive"))
      (node (ref "R11") (pin "2") (pinfunction "2_2") (pintype "passive"))
    )
    (net (code "138") (name "SRV4") (class "Default")
      (node (ref "G1") (pin "PC6") (pinfunction "PC6_PC6") (pintype "bidirectional"))
      (node (ref "JP3") (pin "1") (pinfunction "1_1") (pintype "passive"))
      (node (ref "R10") (pin "2") (pinfunction "2_2") (pintype "passive"))
    )
    (net (code "139") (name "SRV5") (class "Default")
      (node (ref "G1") (pin "PF1-PH1") (pinfunction "PF1-PH1_PF1-PH1") (pintype "bidirectional"))
      (node (ref "JP2") (pin "2") (pinfunction "2_2") (pintype "passive"))
      (node (ref "R9") (pin "2") (pinfunction "2_2") (pintype "passive"))
    )
    (net (code "140") (name "SRV6") (class "Default")
      (node (ref "G1") (pin "PA15") (pinfunction "PA15_PA15") (pintype "bidirectional"))
      (node (ref "JP2") (pin "1") (pinfunction "1_1") (pintype "passive"))
      (node (ref "R8") (pin "2") (pinfunction "2_2") (pintype "passive"))
    )
    (net (code "141") (name "SRV7") (class "Default")
      (node (ref "G1") (pin "PC12") (pinfunction "PC12_PC12") (pintype "bidirectional"))
      (node (ref "JP1") (pin "2") (pinfunction "2_2") (pintype "passive"))
      (node (ref "R7") (pin "2") (pinfunction "2_2") (pintype "passive"))
    )
    (net (code "142") (name "SRV8") (class "Default")
      (node (ref "G1") (pin "PD2") (pinfunction "PD2_PD2") (pintype "bidirectional"))
      (node (ref "JP1") (pin "1") (pinfunction "1_1") (pintype "passive"))
      (node (ref "R6") (pin "2") (pinfunction "2_2") (pintype "passive"))
    )
    (net (code "143") (name "TDRV1") (class "Default")
      (node (ref "G1") (pin "PB12") (pinfunction "PB12_PB12") (pintype "bidirectional"))
      (node (ref "U10") (pin "2") (pinfunction "I_2") (pintype "input"))
      (node (ref "U9") (pin "12") (pinfunction "+IN_12") (pintype "input"))
    )
    (net (code "144") (name "TDRV2") (class "Default")
      (node (ref "G1") (pin "PB2") (pinfunction "PB2_PB2") (pintype "bidirectional"))
      (node (ref "U10") (pin "4") (pinfunction "I_4") (pintype "input"))
      (node (ref "U9") (pin "3") (pinfunction "+IN_3") (pintype "input"))
    )
    (net (code "145") (name "TDRV3") (class "Default")
      (node (ref "G1") (pin "PB15") (pinfunction "PB15_PB15") (pintype "bidirectional"))
      (node (ref "U8") (pin "4") (pinfunction "I_4") (pintype "input"))
      (node (ref "U9") (pin "10") (pinfunction "+IN_10") (pintype "input"))
    )
    (net (code "146") (name "TDRV4") (class "Default")
      (node (ref "G1") (pin "PB1") (pinfunction "PB1_PB1") (pintype "bidirectional"))
      (node (ref "U8") (pin "2") (pinfunction "I_2") (pintype "input"))
      (node (ref "U9") (pin "5") (pinfunction "+IN_5") (pintype "input"))
    )
    (net (code "147") (name "TDRV5") (class "Default")
      (node (ref "G1") (pin "PA0") (pinfunction "PA0_PA0") (pintype "bidirectional"))
      (node (ref "U6") (pin "12") (pinfunction "+IN_12") (pintype "input"))
      (node (ref "U7") (pin "2") (pinfunction "I_2") (pintype "input"))
    )
    (net (code "148") (name "TDRV6") (class "Default")
      (node (ref "G1") (pin "PA4") (pinfunction "PA4_PA4") (pintype "bidirectional"))
      (node (ref "U6") (pin "3") (pinfunction "+IN_3") (pintype "input"))
      (node (ref "U7") (pin "4") (pinfunction "I_4") (pintype "input"))
    )
    (net (code "149") (name "TDRV7") (class "Default")
      (node (ref "G1") (pin "PC3") (pinfunction "PC3_PC3") (pintype "bidirectional"))
      (node (ref "U5") (pin "4") (pinfunction "I_4") (pintype "input"))
      (node (ref "U6") (pin "10") (pinfunction "+IN_10") (pintype "input"))
    )
    (net (code "150") (name "TDRV8") (class "Default")
      (node (ref "G1") (pin "PC0") (pinfunction "PC0_PC0") (pintype "bidirectional"))
      (node (ref "U5") (pin "2") (pinfunction "I_2") (pintype "input"))
      (node (ref "U6") (pin "5") (pinfunction "+IN_5") (pintype "input"))
    )
    (net (code "151") (name "V+") (class "Default")
      (node (ref "C6") (pin "+") (pinfunction "+_+") (pintype "passive"))
      (node (ref "C7") (pin "1") (pinfunction "1_1") (pintype "passive"))
      (node (ref "G1") (pin "E5V") (pinfunction "E5V_E5V") (pintype "power_in"))
      (node (ref "IC1") (pin "1") (pinfunction "FB_1") (pintype "input"))
      (node (ref "L1") (pin "1") (pinfunction "1_1") (pintype "passive"))
      (node (ref "U2") (pin "3") (pinfunction "FB_3") (pintype "bidirectional"))
    )
    (net (code "152") (name "unconnected-(G1-PadBOOT0)") (class "Default")
      (node (ref "G1") (pin "BOOT0") (pinfunction "BOOT0_BOOT0") (pintype "bidirectional"))
    )
    (net (code "153") (name "unconnected-(G1-PadIOREF2)") (class "Default")
      (node (ref "G1") (pin "IOREF2") (pinfunction "IOREF2_IOREF2") (pintype "input"))
    )
    (net (code "154") (name "unconnected-(G1-PadNC1-PF7)") (class "Default")
      (node (ref "G1") (pin "NC1-PF7") (pinfunction "NC1-PF7_NC1-PF7") (pintype "bidirectional"))
    )
    (net (code "155") (name "unconnected-(G1-PadNC2-PF6)") (class "Default")
      (node (ref "G1") (pin "NC2-PF6") (pinfunction "NC2-PF6_NC2-PF6") (pintype "bidirectional"))
    )
    (net (code "156") (name "unconnected-(G1-PadNC3)") (class "Default")
      (node (ref "G1") (pin "NC3") (pinfunction "NC3_NC3") (pintype "no_connect"))
    )
    (net (code "157") (name "unconnected-(G1-PadNC4)") (class "Default")
      (node (ref "G1") (pin "NC4") (pinfunction "NC4_NC4") (pintype "no_connect"))
    )
    (net (code "158") (name "unconnected-(G1-PadNC5-PD8)") (class "Default")
      (node (ref "G1") (pin "NC5-PD8") (pinfunction "NC5-PD8_NC5-PD8") (pintype "bidirectional"))
    )
    (net (code "159") (name "unconnected-(G1-PadNC6-PB11)") (class "Default")
      (node (ref "G1") (pin "NC6-PB11") (pinfunction "NC6-PB11_NC6-PB11") (pintype "no_connect"))
    )
    (net (code "160") (name "unconnected-(G1-PadNC7-PF5)") (class "Default")
      (node (ref "G1") (pin "NC7-PF5") (pinfunction "NC7-PF5_NC7-PF5") (pintype "bidirectional"))
    )
    (net (code "161") (name "unconnected-(G1-PadNC8-PF4)") (class "Default")
      (node (ref "G1") (pin "NC8-PF4") (pinfunction "NC8-PF4_NC8-PF4") (pintype "bidirectional"))
    )
    (net (code "162") (name "unconnected-(G1-PadNRESET)") (class "Default")
      (node (ref "G1") (pin "NRESET") (pinfunction "NRESET_NRESET") (pintype "input"))
    )
    (net (code "163") (name "unconnected-(G1-PadPA1)") (class "Default")
      (node (ref "G1") (pin "PA1") (pinfunction "PA1_PA1") (pintype "bidirectional"))
    )
    (net (code "164") (name "unconnected-(G1-PadPA2)") (class "Default")
      (node (ref "G1") (pin "PA2") (pinfunction "PA2_PA2") (pintype "bidirectional"))
    )
    (net (code "165") (name "unconnected-(G1-PadPA3)") (class "Default")
      (node (ref "G1") (pin "PA3") (pinfunction "PA3_PA3") (pintype "bidirectional"))
    )
    (net (code "166") (name "unconnected-(G1-PadPA5)") (class "Default")
      (node (ref "G1") (pin "PA5") (pinfunction "PA5_PA5") (pintype "bidirectional"))
    )
    (net (code "167") (name "unconnected-(G1-PadPA7)") (class "Default")
      (node (ref "G1") (pin "PA7") (pinfunction "PA7_PA7") (pintype "bidirectional"))
    )
    (net (code "168") (name "unconnected-(G1-PadPA9)") (class "Default")
      (node (ref "G1") (pin "PA9") (pinfunction "PA9_PA9") (pintype "bidirectional"))
    )
    (net (code "169") (name "unconnected-(G1-PadPA10)") (class "Default")
      (node (ref "G1") (pin "PA10") (pinfunction "PA10_PA10") (pintype "bidirectional"))
    )
    (net (code "170") (name "unconnected-(G1-PadPA11)") (class "Default")
      (node (ref "G1") (pin "PA11") (pinfunction "PA11_PA11") (pintype "bidirectional"))
    )
    (net (code "171") (name "unconnected-(G1-PadPA12)") (class "Default")
      (node (ref "G1") (pin "PA12") (pinfunction "PA12_PA12") (pintype "bidirectional"))
    )
    (net (code "172") (name "unconnected-(G1-PadPA13)") (class "Default")
      (node (ref "G1") (pin "PA13") (pinfunction "PA13_PA13") (pintype "bidirectional"))
    )
    (net (code "173") (name "unconnected-(G1-PadPA14)") (class "Default")
      (node (ref "G1") (pin "PA14") (pinfunction "PA14_PA14") (pintype "bidirectional"))
    )
    (net (code "174") (name "unconnected-(G1-PadPB0)") (class "Default")
      (node (ref "G1") (pin "PB0") (pinfunction "PB0_PB0") (pintype "bidirectional"))
    )
    (net (code "175") (name "unconnected-(G1-PadPC1)") (class "Default")
      (node (ref "G1") (pin "PC1") (pinfunction "PC1_PC1") (pintype "bidirectional"))
    )
    (net (code "176") (name "unconnected-(G1-PadPC4)") (class "Default")
      (node (ref "G1") (pin "PC4") (pinfunction "PC4_PC4") (pintype "bidirectional"))
    )
    (net (code "177") (name "unconnected-(G1-PadPC5)") (class "Default")
      (node (ref "G1") (pin "PC5") (pinfunction "PC5_PC5") (pintype "bidirectional"))
    )
    (net (code "178") (name "unconnected-(G1-PadPC13)") (class "Default")
      (node (ref "G1") (pin "PC13") (pinfunction "PC13_PC13") (pintype "bidirectional"))
    )
    (net (code "179") (name "unconnected-(G1-PadPC14)") (class "Default")
      (node (ref "G1") (pin "PC14") (pinfunction "PC14_PC14") (pintype "bidirectional"))
    )
    (net (code "180") (name "unconnected-(G1-PadPC15)") (class "Default")
      (node (ref "G1") (pin "PC15") (pinfunction "PC15_PC15") (pintype "bidirectional"))
    )
    (net (code "181") (name "unconnected-(G1-PadPF0-PH0)") (class "Default")
      (node (ref "G1") (pin "PF0-PH0") (pinfunction "PF0-PH0_PF0-PH0") (pintype "bidirectional"))
    )
    (net (code "182") (name "unconnected-(H1-MOUNT-PadB3,3)") (class "Default")
      (node (ref "H1") (pin "B3,3") (pinfunction "MOUNT_B3,3") (pintype "passive"))
    )
    (net (code "183") (name "unconnected-(H2-MOUNT-PadB3,3)") (class "Default")
      (node (ref "H2") (pin "B3,3") (pinfunction "MOUNT_B3,3") (pintype "passive"))
    )
    (net (code "184") (name "unconnected-(H3-MOUNT-PadB3,3)") (class "Default")
      (node (ref "H3") (pin "B3,3") (pinfunction "MOUNT_B3,3") (pintype "passive"))
    )
    (net (code "185") (name "unconnected-(H4-MOUNT-PadB3,3)") (class "Default")
      (node (ref "H4") (pin "B3,3") (pinfunction "MOUNT_B3,3") (pintype "passive"))
    )
  )
)
